# shcematics.net
KiCad netlist of a schematic drawn in Altium Designer
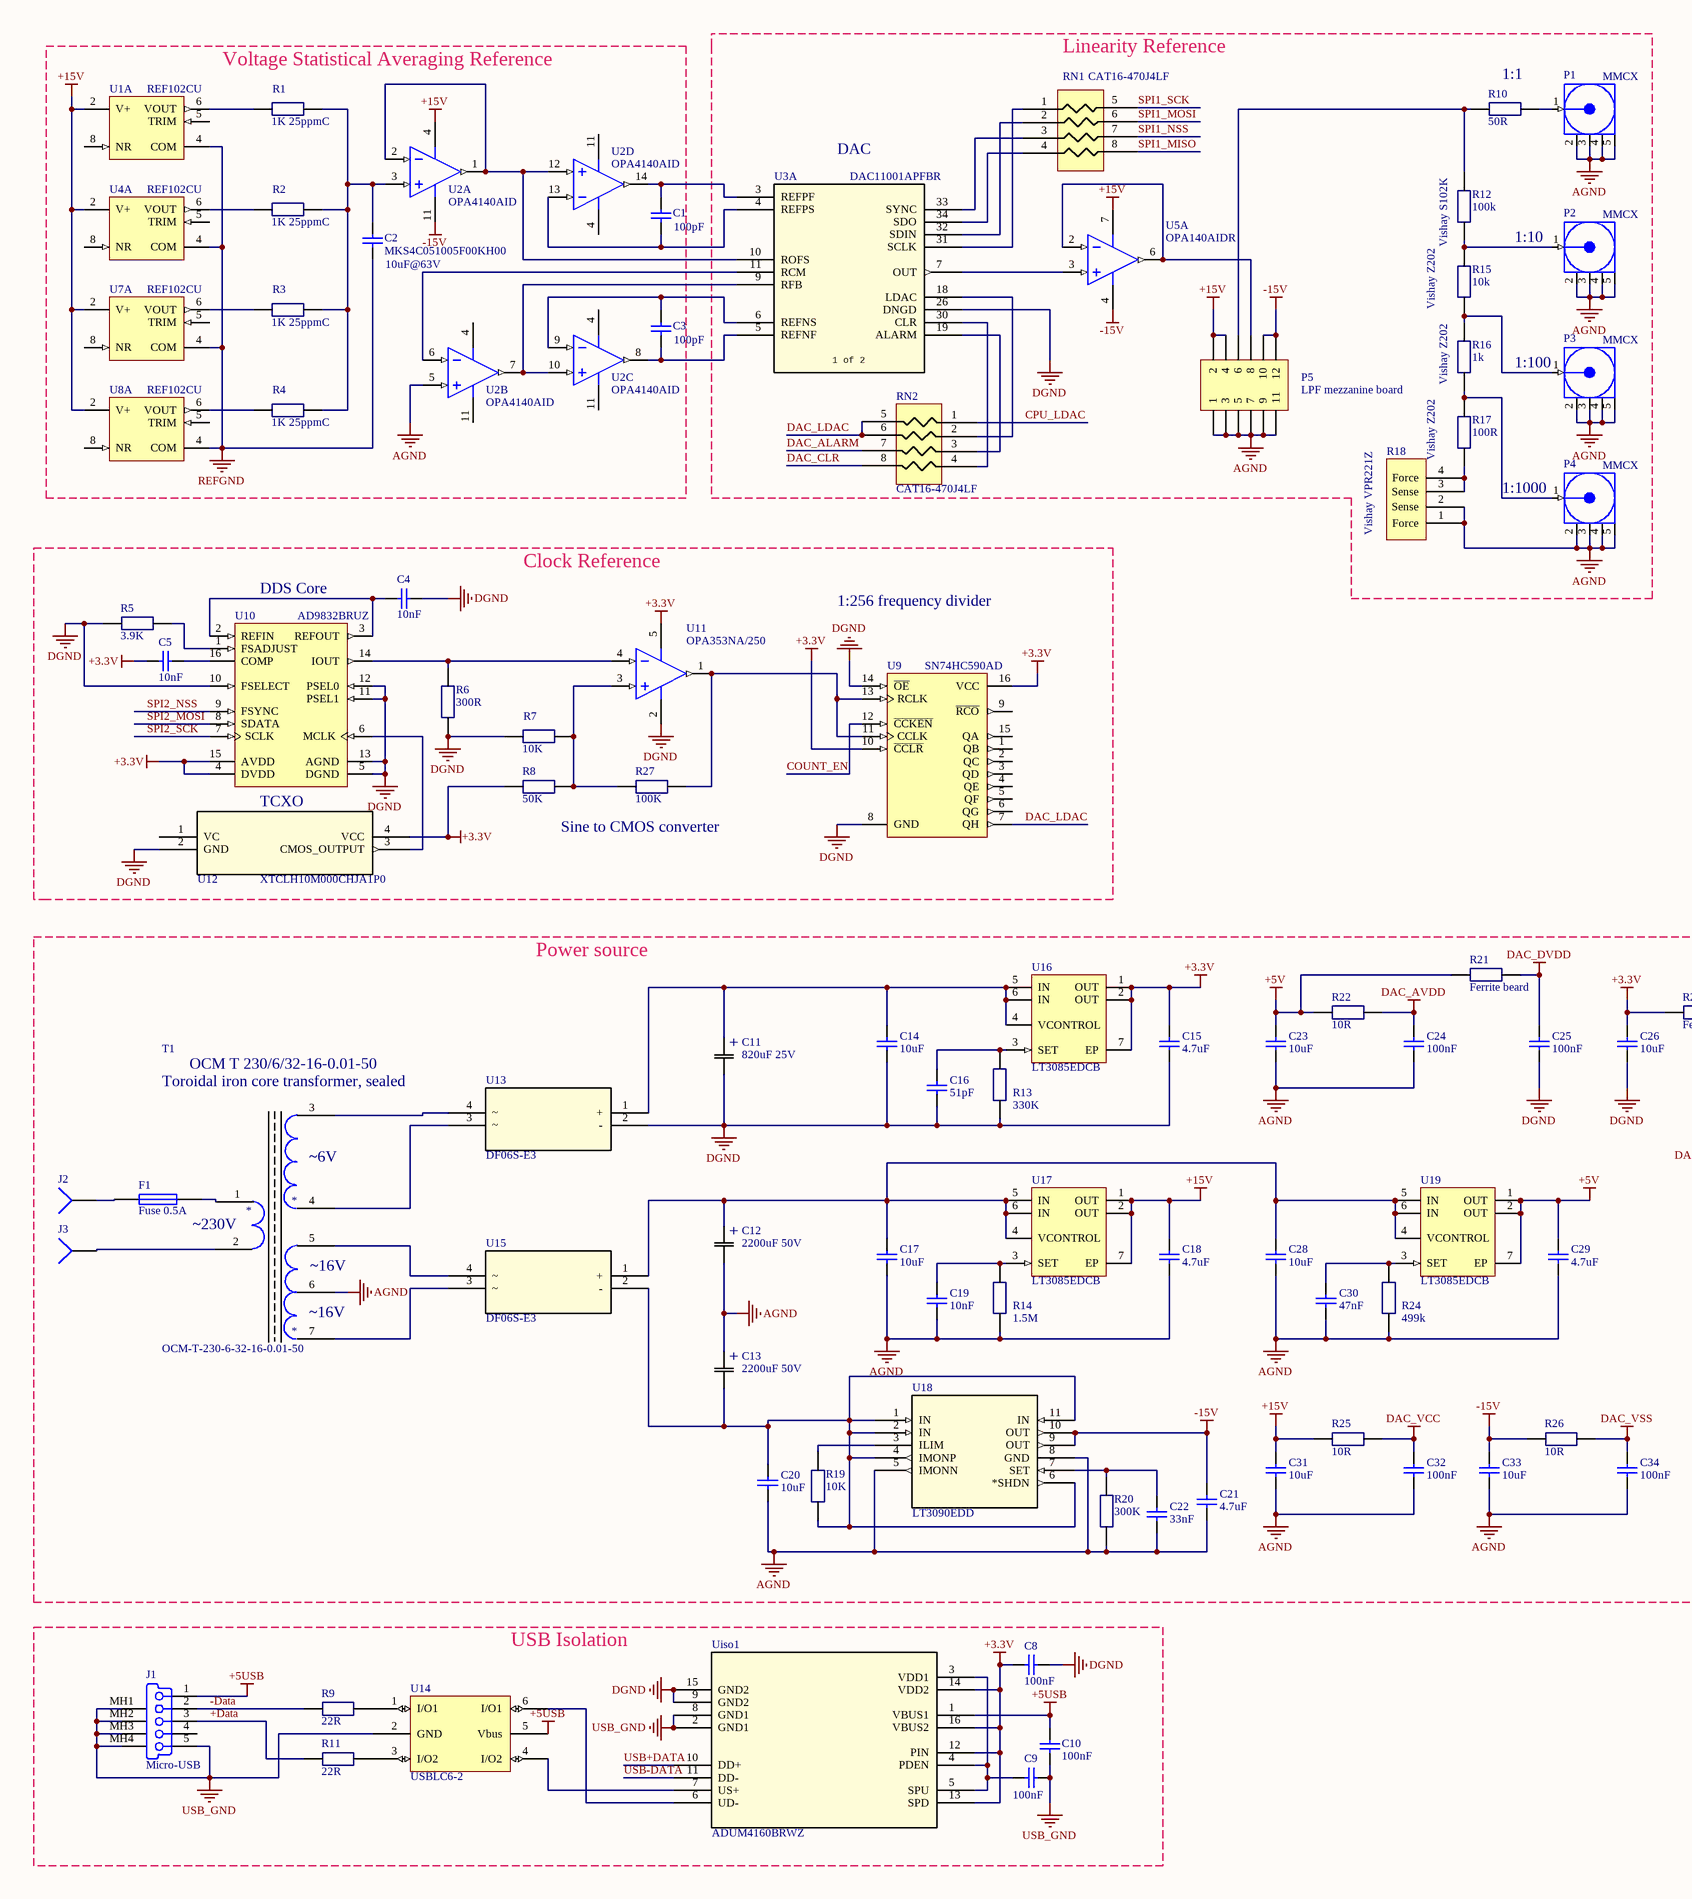
[diagram p0: shcematics.SchDoc, left]
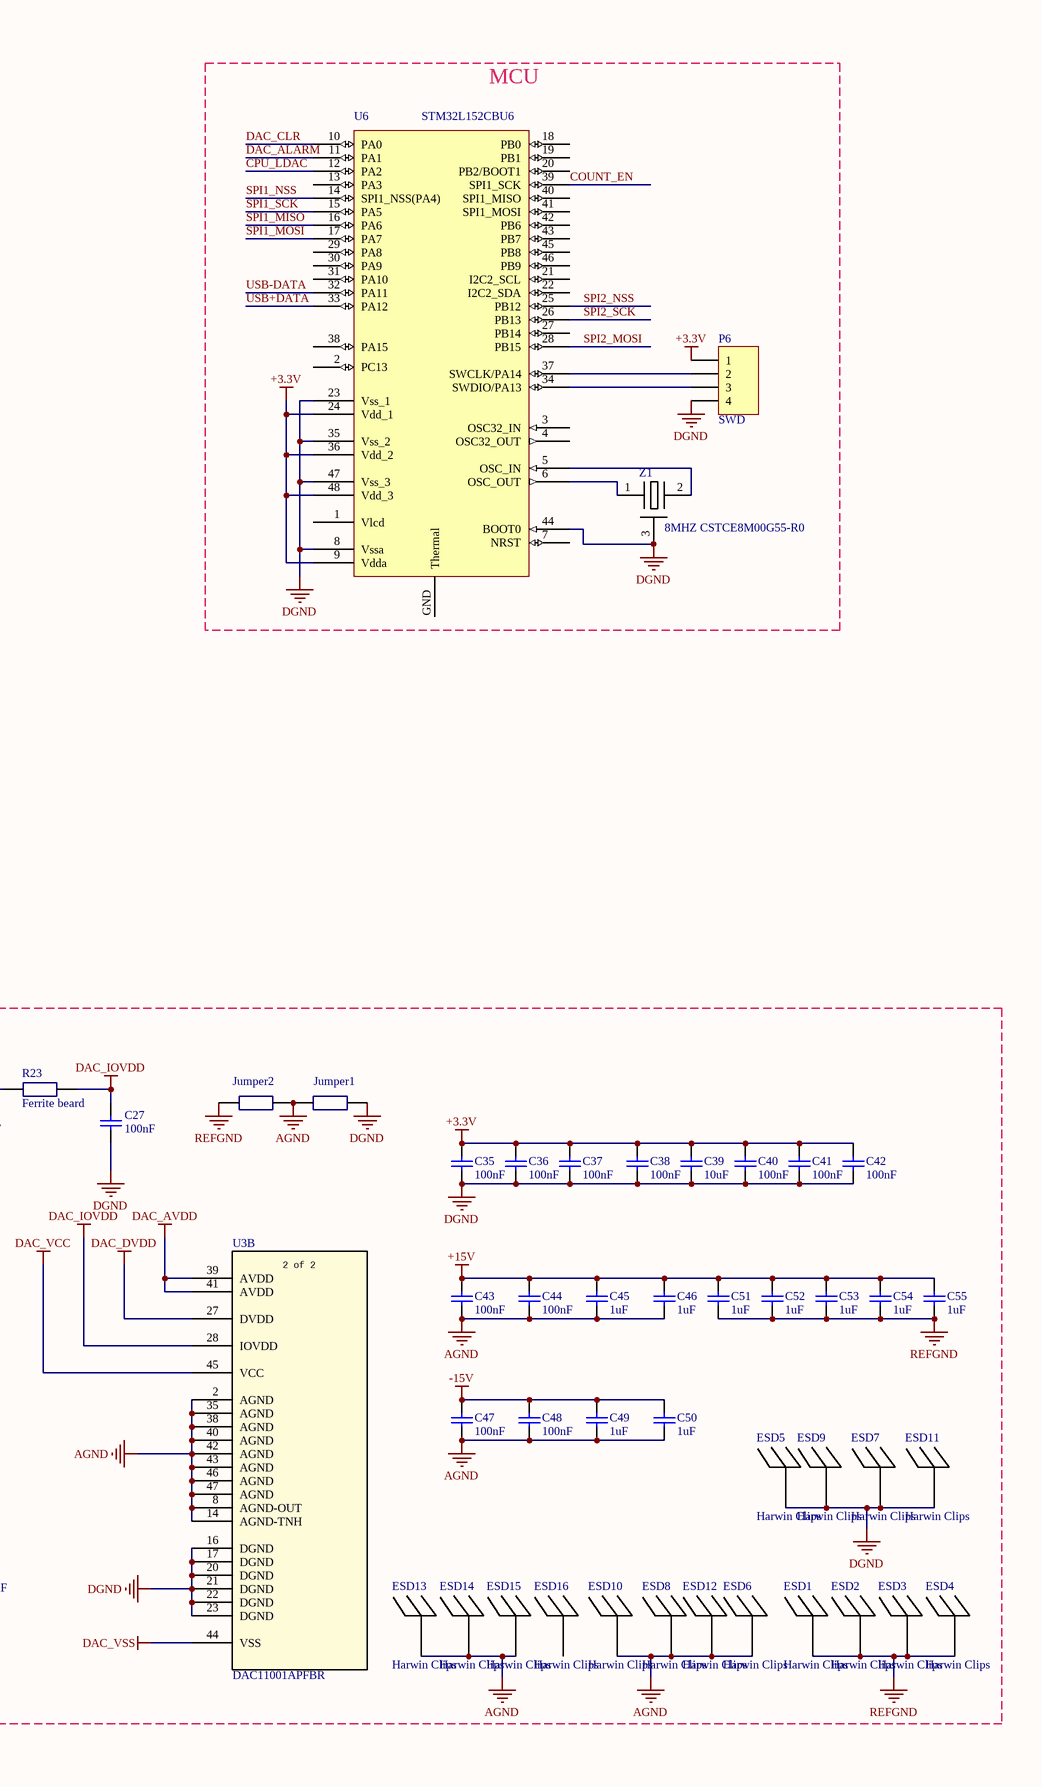
[diagram p1: shcematics.SchDoc, right]

(export (version "E")
  (design (tool "Eeschema 10.0.6"))
  (components
    (comp (ref "C1")
      (value "100pF")
      (footprint "0402")
      (description "Capacitor (Semiconductor SIM Model)")
      (fields (field (name "Comment") "Cap Semi") (field (name "PUBLISHER") "Altium Limited"))
      (libsource (lib "Miscellaneous Devices") (part "Cap Semi"))
    )
    (comp (ref "C2")
      (value "MKS4C051005F00KH00")
      (footprint "MKS4C051005F")
      (description "Capacitor")
      (fields (field (name "ALTIUM_VALUE") "10uF@63V") (field (name "PUBLISHER") "Altium Limited"))
      (libsource (lib "Miscellaneous Devices") (part "Cap"))
    )
    (comp (ref "C3")
      (value "100pF")
      (footprint "0402")
      (description "Capacitor (Semiconductor SIM Model)")
      (fields (field (name "Comment") "Cap Semi") (field (name "PUBLISHER") "Altium Limited"))
      (libsource (lib "Miscellaneous Devices") (part "Cap Semi"))
    )
    (comp (ref "C4")
      (value "10nF")
      (footprint "CAP 0603")
      (description "Capacitor (Semiconductor SIM Model)")
      (fields (field (name "PUBLISHER") "Altium Limited"))
      (libsource (lib "Miscellaneous Devices") (part "Cap Semi"))
    )
    (comp (ref "C5")
      (value "10nF")
      (footprint "CAP 0603")
      (description "Capacitor (Semiconductor SIM Model)")
      (fields (field (name "PUBLISHER") "Altium Limited"))
      (libsource (lib "Miscellaneous Devices") (part "Cap Semi"))
    )
    (comp (ref "C8")
      (value "100nF")
      (footprint "CAP 0603")
      (description "Capacitor (Semiconductor SIM Model)")
      (fields (field (name "PUBLISHER") "Altium Limited"))
      (libsource (lib "Miscellaneous Devices") (part "Cap Semi"))
    )
    (comp (ref "C9")
      (value "100nF")
      (footprint "CAP 0603")
      (description "Capacitor (Semiconductor SIM Model)")
      (fields (field (name "PUBLISHER") "Altium Limited"))
      (libsource (lib "Miscellaneous Devices") (part "Cap Semi"))
    )
    (comp (ref "C10")
      (value "100nF")
      (footprint "CAP 0603")
      (description "Capacitor (Semiconductor SIM Model)")
      (fields (field (name "PUBLISHER") "Altium Limited"))
      (libsource (lib "Miscellaneous Devices") (part "Cap Semi"))
    )
    (comp (ref "C11")
      (value "820uF 25V")
      (footprint "CAP_37M000_TDK")
      (description "No Description Available")
      (fields
        (field (name "MANUFACTURER_PART_NUMBER") "B41858D9337M000")
        (field (name "COPYRIGHT") "Copyright (C) 2018 Accelerated Designs. All rights reserved")
      )
      (libsource (lib "2021-01-20_20-15-04") (part "B41858D9337M000"))
    )
    (comp (ref "C12")
      (value "2200uF 50V")
      (footprint "CAP_37M000_TDK")
      (description "No Description Available")
      (fields
        (field (name "MANUFACTURER_PART_NUMBER") "B41858D9337M000")
        (field (name "COPYRIGHT") "Copyright (C) 2018 Accelerated Designs. All rights reserved")
      )
      (libsource (lib "2021-01-20_20-15-04") (part "B41858D9337M000"))
    )
    (comp (ref "C13")
      (value "2200uF 50V")
      (footprint "CAP_37M000_TDK")
      (description "No Description Available")
      (fields
        (field (name "MANUFACTURER_PART_NUMBER") "B41858D9337M000")
        (field (name "COPYRIGHT") "Copyright (C) 2018 Accelerated Designs. All rights reserved")
      )
      (libsource (lib "2021-01-20_20-15-04") (part "B41858D9337M000"))
    )
    (comp (ref "C14")
      (value "10uF")
      (footprint "C1206")
      (description "Capacitor (Semiconductor SIM Model)")
      (fields (field (name "PUBLISHER") "Altium Limited"))
      (libsource (lib "Miscellaneous Devices") (part "Cap Semi"))
    )
    (comp (ref "C15")
      (value "4.7uF")
      (footprint "C1206")
      (description "Capacitor (Semiconductor SIM Model)")
      (fields (field (name "PUBLISHER") "Altium Limited"))
      (libsource (lib "Miscellaneous Devices") (part "Cap Semi"))
    )
    (comp (ref "C16")
      (value "51pF")
      (footprint "CAP 0603")
      (description "Capacitor (Semiconductor SIM Model)")
      (fields (field (name "PUBLISHER") "Altium Limited"))
      (libsource (lib "Miscellaneous Devices") (part "Cap Semi"))
    )
    (comp (ref "C17")
      (value "10uF")
      (footprint "C1206")
      (description "Capacitor (Semiconductor SIM Model)")
      (fields (field (name "PUBLISHER") "Altium Limited"))
      (libsource (lib "Miscellaneous Devices") (part "Cap Semi"))
    )
    (comp (ref "C18")
      (value "4.7uF")
      (footprint "C1206")
      (description "Capacitor (Semiconductor SIM Model)")
      (fields (field (name "PUBLISHER") "Altium Limited"))
      (libsource (lib "Miscellaneous Devices") (part "Cap Semi"))
    )
    (comp (ref "C19")
      (value "10nF")
      (footprint "CAP 0603")
      (description "Capacitor (Semiconductor SIM Model)")
      (fields (field (name "PUBLISHER") "Altium Limited"))
      (libsource (lib "Miscellaneous Devices") (part "Cap Semi"))
    )
    (comp (ref "C20")
      (value "10uF")
      (footprint "C1206")
      (description "Capacitor (Semiconductor SIM Model)")
      (fields (field (name "PUBLISHER") "Altium Limited"))
      (libsource (lib "Miscellaneous Devices") (part "Cap Semi"))
    )
    (comp (ref "C21")
      (value "4.7uF")
      (footprint "C1206")
      (description "Capacitor (Semiconductor SIM Model)")
      (fields (field (name "PUBLISHER") "Altium Limited"))
      (libsource (lib "Miscellaneous Devices") (part "Cap Semi"))
    )
    (comp (ref "C22")
      (value "33nF")
      (footprint "CAP 0603")
      (description "Capacitor (Semiconductor SIM Model)")
      (fields (field (name "PUBLISHER") "Altium Limited"))
      (libsource (lib "Miscellaneous Devices") (part "Cap Semi"))
    )
    (comp (ref "C23")
      (value "10uF")
      (footprint "CAP 0603")
      (description "Capacitor (Semiconductor SIM Model)")
      (fields (field (name "PUBLISHER") "Altium Limited"))
      (libsource (lib "Miscellaneous Devices") (part "Cap Semi"))
    )
    (comp (ref "C24")
      (value "100nF")
      (footprint "CAP 0603")
      (description "Capacitor (Semiconductor SIM Model)")
      (fields (field (name "PUBLISHER") "Altium Limited"))
      (libsource (lib "Miscellaneous Devices") (part "Cap Semi"))
    )
    (comp (ref "C25")
      (value "100nF")
      (footprint "CAP 0603")
      (description "Capacitor (Semiconductor SIM Model)")
      (fields (field (name "PUBLISHER") "Altium Limited"))
      (libsource (lib "Miscellaneous Devices") (part "Cap Semi"))
    )
    (comp (ref "C26")
      (value "10uF")
      (footprint "CAP 0603")
      (description "Capacitor (Semiconductor SIM Model)")
      (fields (field (name "PUBLISHER") "Altium Limited"))
      (libsource (lib "Miscellaneous Devices") (part "Cap Semi"))
    )
    (comp (ref "C27")
      (value "100nF")
      (footprint "CAP 0603")
      (description "Capacitor (Semiconductor SIM Model)")
      (fields (field (name "PUBLISHER") "Altium Limited"))
      (libsource (lib "Miscellaneous Devices") (part "Cap Semi"))
    )
    (comp (ref "C28")
      (value "10uF")
      (footprint "C1206")
      (description "Capacitor (Semiconductor SIM Model)")
      (fields (field (name "PUBLISHER") "Altium Limited"))
      (libsource (lib "Miscellaneous Devices") (part "Cap Semi"))
    )
    (comp (ref "C29")
      (value "4.7uF")
      (footprint "C1206")
      (description "Capacitor (Semiconductor SIM Model)")
      (fields (field (name "PUBLISHER") "Altium Limited"))
      (libsource (lib "Miscellaneous Devices") (part "Cap Semi"))
    )
    (comp (ref "C30")
      (value "47nF")
      (footprint "CAP 0603")
      (description "Capacitor (Semiconductor SIM Model)")
      (fields (field (name "PUBLISHER") "Altium Limited"))
      (libsource (lib "Miscellaneous Devices") (part "Cap Semi"))
    )
    (comp (ref "C31")
      (value "10uF")
      (footprint "C1206")
      (description "Capacitor (Semiconductor SIM Model)")
      (fields (field (name "PUBLISHER") "Altium Limited"))
      (libsource (lib "Miscellaneous Devices") (part "Cap Semi"))
    )
    (comp (ref "C32")
      (value "100nF")
      (footprint "CAP 0603")
      (description "Capacitor (Semiconductor SIM Model)")
      (fields (field (name "PUBLISHER") "Altium Limited"))
      (libsource (lib "Miscellaneous Devices") (part "Cap Semi"))
    )
    (comp (ref "C33")
      (value "10uF")
      (footprint "C1206")
      (description "Capacitor (Semiconductor SIM Model)")
      (fields (field (name "PUBLISHER") "Altium Limited"))
      (libsource (lib "Miscellaneous Devices") (part "Cap Semi"))
    )
    (comp (ref "C34")
      (value "100nF")
      (footprint "CAP 0603")
      (description "Capacitor (Semiconductor SIM Model)")
      (fields (field (name "PUBLISHER") "Altium Limited"))
      (libsource (lib "Miscellaneous Devices") (part "Cap Semi"))
    )
    (comp (ref "C35")
      (value "100nF")
      (footprint "CAP 0603")
      (description "Capacitor (Semiconductor SIM Model)")
      (fields (field (name "PUBLISHER") "Altium Limited"))
      (libsource (lib "Miscellaneous Devices") (part "Cap Semi"))
    )
    (comp (ref "C36")
      (value "100nF")
      (footprint "CAP 0603")
      (description "Capacitor (Semiconductor SIM Model)")
      (fields (field (name "PUBLISHER") "Altium Limited"))
      (libsource (lib "Miscellaneous Devices") (part "Cap Semi"))
    )
    (comp (ref "C37")
      (value "100nF")
      (footprint "CAP 0603")
      (description "Capacitor (Semiconductor SIM Model)")
      (fields (field (name "PUBLISHER") "Altium Limited"))
      (libsource (lib "Miscellaneous Devices") (part "Cap Semi"))
    )
    (comp (ref "C38")
      (value "100nF")
      (footprint "CAP 0603")
      (description "Capacitor (Semiconductor SIM Model)")
      (fields (field (name "PUBLISHER") "Altium Limited"))
      (libsource (lib "Miscellaneous Devices") (part "Cap Semi"))
    )
    (comp (ref "C39")
      (value "10uF")
      (footprint "CAP 0603")
      (description "Capacitor (Semiconductor SIM Model)")
      (fields (field (name "PUBLISHER") "Altium Limited"))
      (libsource (lib "Miscellaneous Devices") (part "Cap Semi"))
    )
    (comp (ref "C40")
      (value "100nF")
      (footprint "CAP 0603")
      (description "Capacitor (Semiconductor SIM Model)")
      (fields (field (name "PUBLISHER") "Altium Limited"))
      (libsource (lib "Miscellaneous Devices") (part "Cap Semi"))
    )
    (comp (ref "C41")
      (value "100nF")
      (footprint "CAP 0603")
      (description "Capacitor (Semiconductor SIM Model)")
      (fields (field (name "PUBLISHER") "Altium Limited"))
      (libsource (lib "Miscellaneous Devices") (part "Cap Semi"))
    )
    (comp (ref "C42")
      (value "100nF")
      (footprint "CAP 0603")
      (description "Capacitor (Semiconductor SIM Model)")
      (fields (field (name "PUBLISHER") "Altium Limited"))
      (libsource (lib "Miscellaneous Devices") (part "Cap Semi"))
    )
    (comp (ref "C43")
      (value "100nF")
      (footprint "CAP 0603")
      (description "Capacitor (Semiconductor SIM Model)")
      (fields (field (name "PUBLISHER") "Altium Limited"))
      (libsource (lib "Miscellaneous Devices") (part "Cap Semi"))
    )
    (comp (ref "C44")
      (value "100nF")
      (footprint "CAP 0603")
      (description "Capacitor (Semiconductor SIM Model)")
      (fields (field (name "PUBLISHER") "Altium Limited"))
      (libsource (lib "Miscellaneous Devices") (part "Cap Semi"))
    )
    (comp (ref "C45")
      (value "1uF")
      (footprint "CAP 0603")
      (description "Capacitor (Semiconductor SIM Model)")
      (fields (field (name "PUBLISHER") "Altium Limited"))
      (libsource (lib "Miscellaneous Devices") (part "Cap Semi"))
    )
    (comp (ref "C46")
      (value "1uF")
      (footprint "CAP 0603")
      (description "Capacitor (Semiconductor SIM Model)")
      (fields (field (name "PUBLISHER") "Altium Limited"))
      (libsource (lib "Miscellaneous Devices") (part "Cap Semi"))
    )
    (comp (ref "C47")
      (value "100nF")
      (footprint "CAP 0603")
      (description "Capacitor (Semiconductor SIM Model)")
      (fields (field (name "PUBLISHER") "Altium Limited"))
      (libsource (lib "Miscellaneous Devices") (part "Cap Semi"))
    )
    (comp (ref "C48")
      (value "100nF")
      (footprint "CAP 0603")
      (description "Capacitor (Semiconductor SIM Model)")
      (fields (field (name "PUBLISHER") "Altium Limited"))
      (libsource (lib "Miscellaneous Devices") (part "Cap Semi"))
    )
    (comp (ref "C49")
      (value "1uF")
      (footprint "CAP 0603")
      (description "Capacitor (Semiconductor SIM Model)")
      (fields (field (name "PUBLISHER") "Altium Limited"))
      (libsource (lib "Miscellaneous Devices") (part "Cap Semi"))
    )
    (comp (ref "C50")
      (value "1uF")
      (footprint "CAP 0603")
      (description "Capacitor (Semiconductor SIM Model)")
      (fields (field (name "PUBLISHER") "Altium Limited"))
      (libsource (lib "Miscellaneous Devices") (part "Cap Semi"))
    )
    (comp (ref "C51")
      (value "1uF")
      (footprint "CAP 0603")
      (description "Capacitor (Semiconductor SIM Model)")
      (fields (field (name "PUBLISHER") "Altium Limited"))
      (libsource (lib "Miscellaneous Devices") (part "Cap Semi"))
    )
    (comp (ref "C52")
      (value "1uF")
      (footprint "CAP 0603")
      (description "Capacitor (Semiconductor SIM Model)")
      (fields (field (name "PUBLISHER") "Altium Limited"))
      (libsource (lib "Miscellaneous Devices") (part "Cap Semi"))
    )
    (comp (ref "C53")
      (value "1uF")
      (footprint "CAP 0603")
      (description "Capacitor (Semiconductor SIM Model)")
      (fields (field (name "PUBLISHER") "Altium Limited"))
      (libsource (lib "Miscellaneous Devices") (part "Cap Semi"))
    )
    (comp (ref "C54")
      (value "1uF")
      (footprint "CAP 0603")
      (description "Capacitor (Semiconductor SIM Model)")
      (fields (field (name "PUBLISHER") "Altium Limited"))
      (libsource (lib "Miscellaneous Devices") (part "Cap Semi"))
    )
    (comp (ref "C55")
      (value "1uF")
      (footprint "CAP 0603")
      (description "Capacitor (Semiconductor SIM Model)")
      (fields (field (name "PUBLISHER") "Altium Limited"))
      (libsource (lib "Miscellaneous Devices") (part "Cap Semi"))
    )
    (comp (ref "ESD1")
      (value "Harwin Clips")
      (footprint "HARWIN - S0981-46R - CLIP")
      (libsource (lib "My SCH library") (part "Harwin Clips"))
    )
    (comp (ref "ESD2")
      (value "Harwin Clips")
      (footprint "HARWIN - S0981-46R - CLIP")
      (libsource (lib "My SCH library") (part "Harwin Clips"))
    )
    (comp (ref "ESD3")
      (value "Harwin Clips")
      (footprint "HARWIN - S0981-46R - CLIP")
      (libsource (lib "My SCH library") (part "Harwin Clips"))
    )
    (comp (ref "ESD4")
      (value "Harwin Clips")
      (footprint "HARWIN - S0981-46R - CLIP")
      (libsource (lib "My SCH library") (part "Harwin Clips"))
    )
    (comp (ref "ESD5")
      (value "Harwin Clips")
      (footprint "HARWIN - S0981-46R - CLIP")
      (libsource (lib "My SCH library") (part "Harwin Clips"))
    )
    (comp (ref "ESD6")
      (value "Harwin Clips")
      (footprint "HARWIN - S0981-46R - CLIP")
      (libsource (lib "My SCH library") (part "Harwin Clips"))
    )
    (comp (ref "ESD7")
      (value "Harwin Clips")
      (footprint "HARWIN - S0981-46R - CLIP")
      (libsource (lib "My SCH library") (part "Harwin Clips"))
    )
    (comp (ref "ESD8")
      (value "Harwin Clips")
      (footprint "HARWIN - S0981-46R - CLIP")
      (libsource (lib "My SCH library") (part "Harwin Clips"))
    )
    (comp (ref "ESD9")
      (value "Harwin Clips")
      (footprint "HARWIN - S0981-46R - CLIP")
      (libsource (lib "My SCH library") (part "Harwin Clips"))
    )
    (comp (ref "ESD10")
      (value "Harwin Clips")
      (footprint "HARWIN - S0981-46R - CLIP")
      (libsource (lib "My SCH library") (part "Harwin Clips"))
    )
    (comp (ref "ESD11")
      (value "Harwin Clips")
      (footprint "HARWIN - S0981-46R - CLIP")
      (libsource (lib "My SCH library") (part "Harwin Clips"))
    )
    (comp (ref "ESD12")
      (value "Harwin Clips")
      (footprint "HARWIN - S0981-46R - CLIP")
      (libsource (lib "My SCH library") (part "Harwin Clips"))
    )
    (comp (ref "ESD13")
      (value "Harwin Clips")
      (footprint "HARWIN - S0981-46R - CLIP")
      (libsource (lib "My SCH library") (part "Harwin Clips"))
    )
    (comp (ref "ESD14")
      (value "Harwin Clips")
      (footprint "HARWIN - S0981-46R - CLIP")
      (libsource (lib "My SCH library") (part "Harwin Clips"))
    )
    (comp (ref "ESD15")
      (value "Harwin Clips")
      (footprint "HARWIN - S0981-46R - CLIP")
      (libsource (lib "My SCH library") (part "Harwin Clips"))
    )
    (comp (ref "ESD16")
      (value "Harwin Clips")
      (footprint "HARWIN - S0981-46R - CLIP")
      (libsource (lib "My SCH library") (part "Harwin Clips"))
    )
    (comp (ref "F1")
      (value "Fuse 0.5A")
      (footprint "FUSE")
      (description "Fuse")
      (fields (field (name "PUBLISHER") "Altium Limited"))
      (libsource (lib "Miscellaneous Devices") (part "Fuse 1"))
    )
    (comp (ref "J1")
      (value "Micro-USB")
      (footprint "10118193-0001LF")
      (libsource (lib "Molex Serial Bus Mini USB") (part "0481900001"))
    )
    (comp (ref "J2")
      (value "Socket")
      (footprint "PIN1")
      (fields (field (name "PUBLISHER") "Altium Limited"))
      (libsource (lib "Miscellaneous Connectors") (part "Socket"))
    )
    (comp (ref "J3")
      (value "Socket")
      (footprint "PIN1")
      (fields (field (name "PUBLISHER") "Altium Limited"))
      (libsource (lib "Miscellaneous Connectors") (part "Socket"))
    )
    (comp (ref "Jumper1")
      (value "~")
      (footprint "0402 jumper")
      (libsource (lib "Микрон-3") (part "Resistor 0805"))
    )
    (comp (ref "Jumper2")
      (value "~")
      (footprint "0402 jumper")
      (libsource (lib "Микрон-3") (part "Resistor 0805"))
    )
    (comp (ref "P1")
      (value "MMCX")
      (footprint "MMCX2.54-V5")
      (description "RF Coaxial PCB Connector, MMCX; Thru-Hole, Vertical Mount Plug,  50 Ohm Impedance")
      (fields (field (name "PUBLISHER") "Altium Limited"))
      (libsource (lib "Miscellaneous Connectors") (part "COAX-M"))
    )
    (comp (ref "P2")
      (value "MMCX")
      (footprint "MMCX2.54-V5")
      (description "RF Coaxial PCB Connector, MMCX; Thru-Hole, Vertical Mount Plug,  50 Ohm Impedance")
      (fields (field (name "PUBLISHER") "Altium Limited"))
      (libsource (lib "Miscellaneous Connectors") (part "COAX-M"))
    )
    (comp (ref "P3")
      (value "MMCX")
      (footprint "MMCX2.54-V5")
      (description "RF Coaxial PCB Connector, MMCX; Thru-Hole, Vertical Mount Plug,  50 Ohm Impedance")
      (fields (field (name "PUBLISHER") "Altium Limited"))
      (libsource (lib "Miscellaneous Connectors") (part "COAX-M"))
    )
    (comp (ref "P4")
      (value "MMCX")
      (footprint "MMCX2.54-V5")
      (description "RF Coaxial PCB Connector, MMCX; Thru-Hole, Vertical Mount Plug,  50 Ohm Impedance")
      (fields (field (name "PUBLISHER") "Altium Limited"))
      (libsource (lib "Miscellaneous Connectors") (part "COAX-M"))
    )
    (comp (ref "P5")
      (value "LPF mezzanine board")
      (footprint "HDR2X6")
      (description "Header, 6-Pin, Dual row")
      (fields (field (name "PUBLISHER") "Altium Limited"))
      (libsource (lib "Miscellaneous Connectors") (part "Header 6X2"))
    )
    (comp (ref "P6")
      (value "SWD")
      (footprint "HDR1X4")
      (description "Header, 4-Pin")
      (fields (field (name "PUBLISHER") "Altium Limited"))
      (libsource (lib "Miscellaneous Connectors") (part "Header 4"))
    )
    (comp (ref "R1")
      (value "1K 25ppmC")
      (footprint "1608[0603]")
      (libsource (lib "Микрон-3") (part "Resistor 0805"))
    )
    (comp (ref "R2")
      (value "1K 25ppmC")
      (footprint "1608[0603]")
      (libsource (lib "Микрон-3") (part "Resistor 0805"))
    )
    (comp (ref "R3")
      (value "1K 25ppmC")
      (footprint "1608[0603]")
      (libsource (lib "Микрон-3") (part "Resistor 0805"))
    )
    (comp (ref "R4")
      (value "1K 25ppmC")
      (footprint "1608[0603]")
      (libsource (lib "Микрон-3") (part "Resistor 0805"))
    )
    (comp (ref "R5")
      (value "3.9K")
      (footprint "1608[0603]")
      (libsource (lib "Микрон-3") (part "Resistor 0805"))
    )
    (comp (ref "R6")
      (value "300R")
      (footprint "Yegeo 0603")
      (libsource (lib "Микрон-3") (part "Resistor 0805"))
    )
    (comp (ref "R7")
      (value "10K")
      (footprint "Yegeo 0603")
      (libsource (lib "Микрон-3") (part "Resistor 0805"))
    )
    (comp (ref "R8")
      (value "50K")
      (footprint "Yegeo 0603")
      (libsource (lib "Микрон-3") (part "Resistor 0805"))
    )
    (comp (ref "R9")
      (value "22R")
      (footprint "1608[0603]")
      (libsource (lib "Микрон-3") (part "Resistor 0805"))
    )
    (comp (ref "R10")
      (value "50R")
      (footprint "1608[0603]")
      (libsource (lib "Микрон-3") (part "Resistor 0805"))
    )
    (comp (ref "R11")
      (value "22R")
      (footprint "1608[0603]")
      (libsource (lib "Микрон-3") (part "Resistor 0805"))
    )
    (comp (ref "R12")
      (value "100k")
      (footprint "Vishay S102K")
      (fields (field (name "ORDER") "Vishay S102K"))
      (libsource (lib "Микрон-3") (part "Resistor 0805"))
    )
    (comp (ref "R13")
      (value "330K")
      (footprint "1608[0603]")
      (libsource (lib "Микрон-3") (part "Resistor 0805"))
    )
    (comp (ref "R14")
      (value "1.5M")
      (footprint "6-0805_M")
      (libsource (lib "Микрон-3") (part "Resistor 0805"))
    )
    (comp (ref "R15")
      (value "10k")
      (footprint "Vishay Z202")
      (fields (field (name "ORDER") "Vishay Z202"))
      (libsource (lib "Микрон-3") (part "Resistor 0805"))
    )
    (comp (ref "R16")
      (value "1k")
      (footprint "Vishay Z202")
      (fields (field (name "ORDER") "Vishay Z202"))
      (libsource (lib "Микрон-3") (part "Resistor 0805"))
    )
    (comp (ref "R17")
      (value "100R")
      (footprint "Vishay Z202")
      (fields (field (name "ORDER") "Vishay Z202"))
      (libsource (lib "Микрон-3") (part "Resistor 0805"))
    )
    (comp (ref "R18")
      (value "Vishay VPR221Z")
      (footprint "VISHAY VPR221Z")
      (libsource (lib "My SCH library") (part "VISHAY VPR221Z"))
    )
    (comp (ref "R19")
      (value "10K")
      (footprint "1608[0603]")
      (libsource (lib "Микрон-3") (part "Resistor 0805"))
    )
    (comp (ref "R20")
      (value "300K")
      (footprint "1608[0603]")
      (libsource (lib "Микрон-3") (part "Resistor 0805"))
    )
    (comp (ref "R21")
      (value "Ferrite beard")
      (footprint "CC1206JRNPOBBN100")
      (libsource (lib "Микрон-3") (part "Resistor 0805"))
    )
    (comp (ref "R22")
      (value "10R")
      (footprint "1608[0603]")
      (libsource (lib "Микрон-3") (part "Resistor 0805"))
    )
    (comp (ref "R23")
      (value "Ferrite beard")
      (footprint "CC1206JRNPOBBN100")
      (libsource (lib "Микрон-3") (part "Resistor 0805"))
    )
    (comp (ref "R24")
      (value "499k")
      (footprint "1608[0603]")
      (libsource (lib "Микрон-3") (part "Resistor 0805"))
    )
    (comp (ref "R25")
      (value "10R")
      (footprint "1608[0603]")
      (libsource (lib "Микрон-3") (part "Resistor 0805"))
    )
    (comp (ref "R26")
      (value "10R")
      (footprint "1608[0603]")
      (libsource (lib "Микрон-3") (part "Resistor 0805"))
    )
    (comp (ref "R27")
      (value "100K")
      (footprint "Yegeo 0603")
      (libsource (lib "Микрон-3") (part "Resistor 0805"))
    )
    (comp (ref "RN1")
      (value "CAT16-470J4LF")
      (footprint "CAT16-470J4LF")
      (libsource (lib "") (part "CAT16-470J4LF_1"))
    )
    (comp (ref "RN2")
      (value "CAT16-470J4LF")
      (footprint "CAT16-470J4LF")
      (libsource (lib "My SCH library") (part "CAT16-470J4LF"))
    )
    (comp (ref "T1")
      (value "OCM-T-230-6-32-16-0.01-50")
      (footprint "OCM-T-230-6-32-16-0.01-50")
      (libsource (lib "My SCH library") (part "OCM-T-230-6-32-16-0.01-50"))
    )
    (comp (ref "U1")
      (value "REF102CU")
      (footprint "TI-D8_N")
      (description "10 V Precision Voltage Reference, -25 to 85 degC, 8-pin SOIC (D), Green (RoHS & no Sb/Br)")
      (fields (field (name "MANUFACTURER") "Texas Instruments"))
      (libsource (lib "TI Power Management Series Voltage Reference") (part "REF102CU"))
    )
    (comp (ref "U2")
      (value "OPA4140AID")
      (footprint "TI-D14_N")
      (fields (field (name "MANUFACTURER") "Texas Instruments"))
      (libsource (lib "TI Amplifiers and Linear Operational Amplifier Precision Amplifier Part One") (part "OPA4140AID"))
    )
    (comp (ref "U3")
      (value "DAC11001APFBR")
      (footprint "QFP_APFBR_TEX")
      (description "No Description Available")
      (fields (field (name "COPYRIGHT") "Copyright (C) 2018 Accelerated Designs. All rights reserved"))
      (libsource (lib "2021-01-15_13-58-29") (part "DAC11001APFBR"))
    )
    (comp (ref "U4")
      (value "REF102CU")
      (footprint "TI-D8_N")
      (description "10 V Precision Voltage Reference, -25 to 85 degC, 8-pin SOIC (D), Green (RoHS & no Sb/Br)")
      (fields (field (name "MANUFACTURER") "Texas Instruments"))
      (libsource (lib "TI Power Management Series Voltage Reference") (part "REF102CU"))
    )
    (comp (ref "U5")
      (value "OPA140AIDR")
      (footprint "TI-D8_N")
      (fields (field (name "MANUFACTURER") "Texas Instruments"))
      (libsource (lib "TI Amplifiers and Linear Operational Amplifier Precision Amplifier Part One") (part "OPA140AIDR"))
    )
    (comp (ref "U6")
      (value "STM32L152CBU6")
      (footprint "UFQFPN48")
      (libsource (lib "My SCH library") (part "STM32L152CBU6"))
    )
    (comp (ref "U7")
      (value "REF102CU")
      (footprint "TI-D8_N")
      (description "10 V Precision Voltage Reference, -25 to 85 degC, 8-pin SOIC (D), Green (RoHS & no Sb/Br)")
      (fields (field (name "MANUFACTURER") "Texas Instruments"))
      (libsource (lib "TI Power Management Series Voltage Reference") (part "REF102CU"))
    )
    (comp (ref "U8")
      (value "REF102CU")
      (footprint "TI-D8_N")
      (description "10 V Precision Voltage Reference, -25 to 85 degC, 8-pin SOIC (D), Green (RoHS & no Sb/Br)")
      (fields (field (name "MANUFACTURER") "Texas Instruments"))
      (libsource (lib "TI Power Management Series Voltage Reference") (part "REF102CU"))
    )
    (comp (ref "U9")
      (value "SN74HC590AD")
      (footprint "D016_N")
      (description "8-Bit Binary Counter with 3-State Output Registers")
      (fields (field (name "PUBLISHER") "Altium Limited"))
      (libsource (lib "TI Logic Counter") (part "SN74HC590AD"))
    )
    (comp (ref "U10")
      (value "AD9832BRUZ")
      (footprint "ADI-RU-16_N")
      (description "25 MHz Direct Digital Synthesizer, Waveform Generator, 10-Bit, Serial, RU-16, 96 Tube, Pb-Free")
      (libsource (lib "Analog Devices RF IF Direct Digital Synthesis") (part "AD9832BRUZ"))
    )
    (comp (ref "U11")
      (value "OPA353NA/250")
      (footprint "TI-DBV5_N")
      (fields (field (name "MANUFACTURER") "Texas Instruments"))
      (libsource (lib "TI Amplifiers and Linear Operational Amplifier Precision Amplifier Part One") (part "OPA353NA/250"))
    )
    (comp (ref "U12")
      (value "XTCLH10M000CHJA1P0")
      (footprint "XTCLH20M000CHJA0P0_MUR")
      (description "No Description Available")
      (fields
        (field (name "MANUFACTURER_PART_NUMBER") "XTCLH20M000CHJA0P0")
        (field (name "COPYRIGHT") "Copyright (C) 2018 Accelerated Designs. All rights reserved")
      )
      (libsource (lib "2021-01-16_08-30-23") (part "XTCLH20M000CHJA0P0"))
    )
    (comp (ref "U13")
      (value "DF06S-E3")
      (footprint "SO4_DFS_VIS-M")
      (description "No Description Available")
      (fields (field (name "COPYRIGHT") "Copyright (C) 2018 Accelerated Designs. All rights reserved"))
      (libsource (lib "2021-01-20_20-05-57") (part "DF06S-E3"))
    )
    (comp (ref "U14")
      (value "USBLC6-2")
      (footprint "SOT23-6L")
      (libsource (lib "Микрон-3") (part "USBLC6-2"))
    )
    (comp (ref "U15")
      (value "DF06S-E3")
      (footprint "SO4_DFS_VIS-M")
      (description "No Description Available")
      (fields (field (name "COPYRIGHT") "Copyright (C) 2018 Accelerated Designs. All rights reserved"))
      (libsource (lib "2021-01-20_20-05-57") (part "DF06S-E3"))
    )
    (comp (ref "U16")
      (value "LT3085EDCB")
      (footprint "LT-DCB-6_V")
      (fields (field (name "MANUFACTURER") "Linear Technology") (field (name "PARTNUMBER") "LT3085EDCB#PBF"))
      (libsource (lib "Linear Technology Power Management Current Sources") (part "LT3085EDCB#PBF"))
    )
    (comp (ref "U17")
      (value "LT3085EDCB")
      (footprint "LT-DCB-6_V")
      (fields (field (name "MANUFACTURER") "Linear Technology") (field (name "PARTNUMBER") "LT3085EDCB#PBF"))
      (libsource (lib "Linear Technology Power Management Current Sources") (part "LT3085EDCB#PBF"))
    )
    (comp (ref "U18")
      (value "LT3090EDD")
      (footprint "DFN-10_DD")
      (description "Imported")
      (fields (field (name "MANUFACTURER_PART_NUMBER") "lt3090edd#pbf"))
      (libsource (lib "2017-08-07_08-21-16") (part "LT3090EDDPBF"))
    )
    (comp (ref "U19")
      (value "LT3085EDCB")
      (footprint "LT-DCB-6_V")
      (fields (field (name "MANUFACTURER") "Linear Technology") (field (name "PARTNUMBER") "LT3085EDCB#PBF"))
      (libsource (lib "Linear Technology Power Management Current Sources") (part "LT3085EDCB#PBF"))
    )
    (comp (ref "Uiso1")
      (value "ADUM4160BRWZ")
      (footprint "RW_16_ADI")
      (description "No Description Available")
      (fields (field (name "COPYRIGHT") "Copyright (C) 2018 Accelerated Designs. All rights reserved"))
      (libsource (lib "2021-01-20_09-44-58") (part "ADUM4160BRWZ"))
    )
    (comp (ref "Z1")
      (value "8MHZ CSTCE8M00G55-R0")
      (footprint "PRQV8.00CR5010Y000")
      (libsource (lib "My SCH library") (part "8MHZ_cap"))
    )
  )
  (nets
    (net (code "1") (name "+3.3V") (class "Default")
      (node (ref "C15") (pin "1") (pinfunction "1_1") (pintype "passive"))
      (node (ref "C26") (pin "1") (pinfunction "1_1") (pintype "passive"))
      (node (ref "C35") (pin "2") (pinfunction "2_2") (pintype "passive"))
      (node (ref "C36") (pin "2") (pinfunction "2_2") (pintype "passive"))
      (node (ref "C37") (pin "2") (pinfunction "2_2") (pintype "passive"))
      (node (ref "C38") (pin "2") (pinfunction "2_2") (pintype "passive"))
      (node (ref "C39") (pin "2") (pinfunction "2_2") (pintype "passive"))
      (node (ref "C40") (pin "2") (pinfunction "2_2") (pintype "passive"))
      (node (ref "C41") (pin "2") (pinfunction "2_2") (pintype "passive"))
      (node (ref "C42") (pin "2") (pinfunction "2_2") (pintype "passive"))
      (node (ref "C5") (pin "1") (pinfunction "1_1") (pintype "passive"))
      (node (ref "C8") (pin "2") (pinfunction "2_2") (pintype "passive"))
      (node (ref "P6") (pin "1") (pinfunction "1_1") (pintype "passive"))
      (node (ref "R23") (pin "2") (pinfunction "2_2") (pintype "passive"))
      (node (ref "R8") (pin "2") (pinfunction "2_2") (pintype "passive"))
      (node (ref "U10") (pin "15") (pinfunction "AVDD_15") (pintype "power_in"))
      (node (ref "U10") (pin "4") (pinfunction "DVDD_4") (pintype "power_in"))
      (node (ref "U11") (pin "5") (pinfunction "V+_5") (pintype "power_in"))
      (node (ref "U12") (pin "4") (pinfunction "VCC_4") (pintype "power_in"))
      (node (ref "U16") (pin "1") (pinfunction "OUT_1") (pintype "power_in"))
      (node (ref "U16") (pin "2") (pinfunction "OUT_2") (pintype "power_in"))
      (node (ref "U16") (pin "7") (pinfunction "EP_7") (pintype "power_in"))
      (node (ref "U6") (pin "24") (pinfunction "Vdd_1_24") (pintype "power_in"))
      (node (ref "U6") (pin "36") (pinfunction "Vdd_2_36") (pintype "power_in"))
      (node (ref "U6") (pin "48") (pinfunction "Vdd_3_48") (pintype "power_in"))
      (node (ref "U6") (pin "9") (pinfunction "Vdda_9") (pintype "power_in"))
      (node (ref "U9") (pin "10") (pinfunction "~{CCLR}_10") (pintype "input"))
      (node (ref "U9") (pin "16") (pinfunction "VCC_16") (pintype "power_in"))
      (node (ref "Uiso1") (pin "12") (pinfunction "PIN_12") (pintype "passive"))
      (node (ref "Uiso1") (pin "13") (pinfunction "SPD_13") (pintype "passive"))
      (node (ref "Uiso1") (pin "14") (pinfunction "VDD2_14") (pintype "passive"))
      (node (ref "Uiso1") (pin "16") (pinfunction "VBUS2_16") (pintype "passive"))
    )
    (net (code "2") (name "+5USB") (class "Default")
      (node (ref "C10") (pin "2") (pinfunction "2_2") (pintype "passive"))
      (node (ref "J1") (pin "1") (pinfunction "V_BUS_(5V)_1") (pintype "passive"))
      (node (ref "U14") (pin "5") (pinfunction "Vbus_5") (pintype "power_in"))
      (node (ref "Uiso1") (pin "1") (pinfunction "VBUS1_1") (pintype "passive"))
    )
    (net (code "3") (name "+5V") (class "Default")
      (node (ref "C23") (pin "1") (pinfunction "1_1") (pintype "passive"))
      (node (ref "C29") (pin "1") (pinfunction "1_1") (pintype "passive"))
      (node (ref "R21") (pin "2") (pinfunction "2_2") (pintype "passive"))
      (node (ref "R22") (pin "2") (pinfunction "2_2") (pintype "passive"))
      (node (ref "U19") (pin "1") (pinfunction "OUT_1") (pintype "power_in"))
      (node (ref "U19") (pin "2") (pinfunction "OUT_2") (pintype "power_in"))
      (node (ref "U19") (pin "7") (pinfunction "EP_7") (pintype "power_in"))
    )
    (net (code "4") (name "+15V") (class "Default")
      (node (ref "C18") (pin "1") (pinfunction "1_1") (pintype "passive"))
      (node (ref "C31") (pin "1") (pinfunction "1_1") (pintype "passive"))
      (node (ref "C43") (pin "2") (pinfunction "2_2") (pintype "passive"))
      (node (ref "C44") (pin "2") (pinfunction "2_2") (pintype "passive"))
      (node (ref "C45") (pin "2") (pinfunction "2_2") (pintype "passive"))
      (node (ref "C46") (pin "2") (pinfunction "2_2") (pintype "passive"))
      (node (ref "C51") (pin "2") (pinfunction "2_2") (pintype "passive"))
      (node (ref "C52") (pin "2") (pinfunction "2_2") (pintype "passive"))
      (node (ref "C53") (pin "2") (pinfunction "2_2") (pintype "passive"))
      (node (ref "C54") (pin "2") (pinfunction "2_2") (pintype "passive"))
      (node (ref "C55") (pin "2") (pinfunction "2_2") (pintype "passive"))
      (node (ref "P5") (pin "2") (pinfunction "2_2") (pintype "passive"))
      (node (ref "P5") (pin "4") (pinfunction "4_4") (pintype "passive"))
      (node (ref "R25") (pin "2") (pinfunction "2_2") (pintype "passive"))
      (node (ref "U1") (pin "2") (pinfunction "V+_2") (pintype "power_in"))
      (node (ref "U17") (pin "1") (pinfunction "OUT_1") (pintype "power_in"))
      (node (ref "U17") (pin "2") (pinfunction "OUT_2") (pintype "power_in"))
      (node (ref "U17") (pin "7") (pinfunction "EP_7") (pintype "power_in"))
      (node (ref "U2") (pin "4") (pinfunction "V+_4") (pintype "power_in"))
      (node (ref "U4") (pin "2") (pinfunction "V+_2") (pintype "power_in"))
      (node (ref "U5") (pin "7") (pinfunction "V+_7") (pintype "power_in"))
      (node (ref "U7") (pin "2") (pinfunction "V+_2") (pintype "power_in"))
      (node (ref "U8") (pin "2") (pinfunction "V+_2") (pintype "power_in"))
    )
    (net (code "5") (name "-15V") (class "Default")
      (node (ref "C21") (pin "1") (pinfunction "1_1") (pintype "passive"))
      (node (ref "C33") (pin "1") (pinfunction "1_1") (pintype "passive"))
      (node (ref "C47") (pin "2") (pinfunction "2_2") (pintype "passive"))
      (node (ref "C48") (pin "2") (pinfunction "2_2") (pintype "passive"))
      (node (ref "C49") (pin "2") (pinfunction "2_2") (pintype "passive"))
      (node (ref "C50") (pin "2") (pinfunction "2_2") (pintype "passive"))
      (node (ref "P5") (pin "10") (pinfunction "10_10") (pintype "passive"))
      (node (ref "P5") (pin "12") (pinfunction "12_12") (pintype "passive"))
      (node (ref "R26") (pin "2") (pinfunction "2_2") (pintype "passive"))
      (node (ref "U18") (pin "10") (pinfunction "OUT_10") (pintype "output"))
      (node (ref "U18") (pin "9") (pinfunction "OUT_9") (pintype "output"))
      (node (ref "U2") (pin "11") (pinfunction "V-_11") (pintype "power_in"))
      (node (ref "U5") (pin "4") (pinfunction "V-_4") (pintype "power_in"))
    )
    (net (code "6") (name "/+Data") (class "Default")
      (node (ref "J1") (pin "3") (pinfunction "D+_3") (pintype "passive"))
      (node (ref "R11") (pin "2") (pinfunction "2_2") (pintype "passive"))
    )
    (net (code "7") (name "/-Data") (class "Default")
      (node (ref "J1") (pin "2") (pinfunction "D-_2") (pintype "passive"))
      (node (ref "R9") (pin "2") (pinfunction "2_2") (pintype "passive"))
    )
    (net (code "8") (name "/COUNT_EN") (class "Default")
      (node (ref "U6") (pin "39") (pinfunction "SPI1_SCK_39") (pintype "bidirectional"))
      (node (ref "U9") (pin "12") (pinfunction "~{CCKEN}_12") (pintype "input"))
    )
    (net (code "9") (name "/CPU_LDAC") (class "Default")
      (node (ref "RN2") (pin "1") (pinfunction "1_1") (pintype "passive"))
      (node (ref "U6") (pin "12") (pinfunction "PA2_12") (pintype "bidirectional"))
    )
    (net (code "10") (name "/DAC_ALARM") (class "Default")
      (node (ref "RN2") (pin "7") (pinfunction "7_7") (pintype "passive"))
      (node (ref "U6") (pin "11") (pinfunction "PA1_11") (pintype "bidirectional"))
    )
    (net (code "11") (name "/DAC_CLR") (class "Default")
      (node (ref "RN2") (pin "8") (pinfunction "8_8") (pintype "passive"))
      (node (ref "U6") (pin "10") (pinfunction "PA0_10") (pintype "bidirectional"))
    )
    (net (code "12") (name "/DAC_LDAC") (class "Default")
      (node (ref "RN2") (pin "5") (pinfunction "5_5") (pintype "passive"))
      (node (ref "RN2") (pin "6") (pinfunction "6_6") (pintype "passive"))
      (node (ref "U9") (pin "7") (pinfunction "QH_7") (pintype "output"))
    )
    (net (code "13") (name "/SPI1_MISO") (class "Default")
      (node (ref "RN1") (pin "8") (pinfunction "8_8") (pintype "passive"))
      (node (ref "U6") (pin "16") (pinfunction "PA6_16") (pintype "bidirectional"))
    )
    (net (code "14") (name "/SPI1_MOSI") (class "Default")
      (node (ref "RN1") (pin "6") (pinfunction "6_6") (pintype "passive"))
      (node (ref "U6") (pin "17") (pinfunction "PA7_17") (pintype "bidirectional"))
    )
    (net (code "15") (name "/SPI1_NSS") (class "Default")
      (node (ref "RN1") (pin "7") (pinfunction "7_7") (pintype "passive"))
      (node (ref "U6") (pin "14") (pinfunction "SPI1_NSS(PA4)_14") (pintype "bidirectional"))
    )
    (net (code "16") (name "/SPI1_SCK") (class "Default")
      (node (ref "RN1") (pin "5") (pinfunction "5_5") (pintype "passive"))
      (node (ref "U6") (pin "15") (pinfunction "PA5_15") (pintype "bidirectional"))
    )
    (net (code "17") (name "/SPI2_MOSI") (class "Default")
      (node (ref "U10") (pin "8") (pinfunction "SDATA_8") (pintype "input"))
      (node (ref "U6") (pin "28") (pinfunction "PB15_28") (pintype "bidirectional"))
    )
    (net (code "18") (name "/SPI2_NSS") (class "Default")
      (node (ref "U10") (pin "9") (pinfunction "FSYNC_9") (pintype "input"))
      (node (ref "U6") (pin "25") (pinfunction "PB12_25") (pintype "bidirectional"))
    )
    (net (code "19") (name "/SPI2_SCK") (class "Default")
      (node (ref "U10") (pin "7") (pinfunction "SCLK_7") (pintype "input"))
      (node (ref "U6") (pin "26") (pinfunction "PB13_26") (pintype "bidirectional"))
    )
    (net (code "20") (name "/USB+DATA") (class "Default")
      (node (ref "U6") (pin "33") (pinfunction "PA12_33") (pintype "bidirectional"))
      (node (ref "Uiso1") (pin "10") (pinfunction "DD+_10") (pintype "passive"))
    )
    (net (code "21") (name "/USB-DATA") (class "Default")
      (node (ref "U6") (pin "32") (pinfunction "PA11_32") (pintype "bidirectional"))
      (node (ref "Uiso1") (pin "11") (pinfunction "DD-_11") (pintype "passive"))
    )
    (net (code "22") (name "AGND") (class "Default")
      (node (ref "C12") (pin "2") (pinfunction "2_2") (pintype "passive"))
      (node (ref "C13") (pin "1") (pinfunction "1_1") (pintype "passive"))
      (node (ref "C17") (pin "2") (pinfunction "2_2") (pintype "passive"))
      (node (ref "C18") (pin "2") (pinfunction "2_2") (pintype "passive"))
      (node (ref "C19") (pin "2") (pinfunction "2_2") (pintype "passive"))
      (node (ref "C20") (pin "2") (pinfunction "2_2") (pintype "passive"))
      (node (ref "C21") (pin "2") (pinfunction "2_2") (pintype "passive"))
      (node (ref "C22") (pin "2") (pinfunction "2_2") (pintype "passive"))
      (node (ref "C23") (pin "2") (pinfunction "2_2") (pintype "passive"))
      (node (ref "C24") (pin "2") (pinfunction "2_2") (pintype "passive"))
      (node (ref "C28") (pin "2") (pinfunction "2_2") (pintype "passive"))
      (node (ref "C29") (pin "2") (pinfunction "2_2") (pintype "passive"))
      (node (ref "C30") (pin "2") (pinfunction "2_2") (pintype "passive"))
      (node (ref "C31") (pin "2") (pinfunction "2_2") (pintype "passive"))
      (node (ref "C32") (pin "2") (pinfunction "2_2") (pintype "passive"))
      (node (ref "C33") (pin "2") (pinfunction "2_2") (pintype "passive"))
      (node (ref "C34") (pin "2") (pinfunction "2_2") (pintype "passive"))
      (node (ref "C43") (pin "1") (pinfunction "1_1") (pintype "passive"))
      (node (ref "C44") (pin "1") (pinfunction "1_1") (pintype "passive"))
      (node (ref "C45") (pin "1") (pinfunction "1_1") (pintype "passive"))
      (node (ref "C46") (pin "1") (pinfunction "1_1") (pintype "passive"))
      (node (ref "C47") (pin "1") (pinfunction "1_1") (pintype "passive"))
      (node (ref "C48") (pin "1") (pinfunction "1_1") (pintype "passive"))
      (node (ref "C49") (pin "1") (pinfunction "1_1") (pintype "passive"))
      (node (ref "C50") (pin "1") (pinfunction "1_1") (pintype "passive"))
      (node (ref "ESD10") (pin "1") (pinfunction "1_1") (pintype "passive"))
      (node (ref "ESD12") (pin "1") (pinfunction "1_1") (pintype "passive"))
      (node (ref "ESD13") (pin "1") (pinfunction "1_1") (pintype "passive"))
      (node (ref "ESD14") (pin "1") (pinfunction "1_1") (pintype "passive"))
      (node (ref "ESD15") (pin "1") (pinfunction "1_1") (pintype "passive"))
      (node (ref "ESD6") (pin "1") (pinfunction "1_1") (pintype "passive"))
      (node (ref "ESD8") (pin "1") (pinfunction "1_1") (pintype "passive"))
      (node (ref "Jumper1") (pin "2") (pinfunction "2_2") (pintype "passive"))
      (node (ref "Jumper2") (pin "2") (pinfunction "2_2") (pintype "passive"))
      (node (ref "P1") (pin "2") (pinfunction "GND_2") (pintype "power_in"))
      (node (ref "P1") (pin "3") (pinfunction "GND_3") (pintype "power_in"))
      (node (ref "P1") (pin "4") (pinfunction "GND_4") (pintype "power_in"))
      (node (ref "P1") (pin "5") (pinfunction "GND_5") (pintype "power_in"))
      (node (ref "P2") (pin "2") (pinfunction "GND_2") (pintype "power_in"))
      (node (ref "P2") (pin "3") (pinfunction "GND_3") (pintype "power_in"))
      (node (ref "P2") (pin "4") (pinfunction "GND_4") (pintype "power_in"))
      (node (ref "P2") (pin "5") (pinfunction "GND_5") (pintype "power_in"))
      (node (ref "P3") (pin "2") (pinfunction "GND_2") (pintype "power_in"))
      (node (ref "P3") (pin "3") (pinfunction "GND_3") (pintype "power_in"))
      (node (ref "P3") (pin "4") (pinfunction "GND_4") (pintype "power_in"))
      (node (ref "P3") (pin "5") (pinfunction "GND_5") (pintype "power_in"))
      (node (ref "P4") (pin "2") (pinfunction "GND_2") (pintype "power_in"))
      (node (ref "P4") (pin "3") (pinfunction "GND_3") (pintype "power_in"))
      (node (ref "P4") (pin "4") (pinfunction "GND_4") (pintype "power_in"))
      (node (ref "P4") (pin "5") (pinfunction "GND_5") (pintype "power_in"))
      (node (ref "P5") (pin "1") (pinfunction "1_1") (pintype "passive"))
      (node (ref "P5") (pin "11") (pinfunction "11_11") (pintype "passive"))
      (node (ref "P5") (pin "3") (pinfunction "3_3") (pintype "passive"))
      (node (ref "P5") (pin "5") (pinfunction "5_5") (pintype "passive"))
      (node (ref "P5") (pin "7") (pinfunction "7_7") (pintype "passive"))
      (node (ref "P5") (pin "9") (pinfunction "9_9") (pintype "passive"))
      (node (ref "R14") (pin "2") (pinfunction "2_2") (pintype "passive"))
      (node (ref "R18") (pin "1") (pinfunction "Force_1") (pintype "passive"))
      (node (ref "R18") (pin "2") (pinfunction "Sense_2") (pintype "passive"))
      (node (ref "R20") (pin "1") (pinfunction "A_1") (pintype "passive"))
      (node (ref "R24") (pin "2") (pinfunction "2_2") (pintype "passive"))
      (node (ref "T1") (pin "6") (pinfunction "6_6") (pintype "passive"))
      (node (ref "U18") (pin "5") (pinfunction "IMONN_5") (pintype "output"))
      (node (ref "U18") (pin "8") (pinfunction "GND_8") (pintype "power_in"))
      (node (ref "U2") (pin "5") (pinfunction "IN_B+_5") (pintype "input"))
      (node (ref "U3") (pin "14") (pinfunction "AGND-TNH_14") (pintype "passive"))
      (node (ref "U3") (pin "2") (pinfunction "AGND_2") (pintype "passive"))
      (node (ref "U3") (pin "35") (pinfunction "AGND_35") (pintype "passive"))
      (node (ref "U3") (pin "38") (pinfunction "AGND_38") (pintype "passive"))
      (node (ref "U3") (pin "40") (pinfunction "AGND_40") (pintype "passive"))
      (node (ref "U3") (pin "42") (pinfunction "AGND_42") (pintype "passive"))
      (node (ref "U3") (pin "43") (pinfunction "AGND_43") (pintype "passive"))
      (node (ref "U3") (pin "46") (pinfunction "AGND_46") (pintype "passive"))
      (node (ref "U3") (pin "47") (pinfunction "AGND_47") (pintype "passive"))
      (node (ref "U3") (pin "8") (pinfunction "AGND-OUT_8") (pintype "passive"))
    )
    (net (code "23") (name "DAC_AVDD") (class "Default")
      (node (ref "C24") (pin "1") (pinfunction "1_1") (pintype "passive"))
      (node (ref "R22") (pin "1") (pinfunction "A_1") (pintype "passive"))
      (node (ref "U3") (pin "39") (pinfunction "AVDD_39") (pintype "power_in"))
      (node (ref "U3") (pin "41") (pinfunction "AVDD_41") (pintype "power_in"))
    )
    (net (code "24") (name "DAC_DVDD") (class "Default")
      (node (ref "C25") (pin "1") (pinfunction "1_1") (pintype "passive"))
      (node (ref "R21") (pin "1") (pinfunction "A_1") (pintype "passive"))
      (node (ref "U3") (pin "27") (pinfunction "DVDD_27") (pintype "power_in"))
    )
    (net (code "25") (name "DAC_IOVDD") (class "Default")
      (node (ref "C27") (pin "1") (pinfunction "1_1") (pintype "passive"))
      (node (ref "R23") (pin "1") (pinfunction "A_1") (pintype "passive"))
      (node (ref "U3") (pin "28") (pinfunction "IOVDD_28") (pintype "power_in"))
    )
    (net (code "26") (name "DAC_VCC") (class "Default")
      (node (ref "C32") (pin "1") (pinfunction "1_1") (pintype "passive"))
      (node (ref "R25") (pin "1") (pinfunction "A_1") (pintype "passive"))
      (node (ref "U3") (pin "45") (pinfunction "VCC_45") (pintype "power_in"))
    )
    (net (code "27") (name "DAC_VSS") (class "Default")
      (node (ref "C34") (pin "1") (pinfunction "1_1") (pintype "passive"))
      (node (ref "R26") (pin "1") (pinfunction "A_1") (pintype "passive"))
      (node (ref "U3") (pin "44") (pinfunction "VSS_44") (pintype "passive"))
    )
    (net (code "28") (name "DGND") (class "Default")
      (node (ref "C11") (pin "2") (pinfunction "2_2") (pintype "passive"))
      (node (ref "C14") (pin "2") (pinfunction "2_2") (pintype "passive"))
      (node (ref "C15") (pin "2") (pinfunction "2_2") (pintype "passive"))
      (node (ref "C16") (pin "2") (pinfunction "2_2") (pintype "passive"))
      (node (ref "C25") (pin "2") (pinfunction "2_2") (pintype "passive"))
      (node (ref "C26") (pin "2") (pinfunction "2_2") (pintype "passive"))
      (node (ref "C27") (pin "2") (pinfunction "2_2") (pintype "passive"))
      (node (ref "C35") (pin "1") (pinfunction "1_1") (pintype "passive"))
      (node (ref "C36") (pin "1") (pinfunction "1_1") (pintype "passive"))
      (node (ref "C37") (pin "1") (pinfunction "1_1") (pintype "passive"))
      (node (ref "C38") (pin "1") (pinfunction "1_1") (pintype "passive"))
      (node (ref "C39") (pin "1") (pinfunction "1_1") (pintype "passive"))
      (node (ref "C4") (pin "2") (pinfunction "2_2") (pintype "passive"))
      (node (ref "C40") (pin "1") (pinfunction "1_1") (pintype "passive"))
      (node (ref "C41") (pin "1") (pinfunction "1_1") (pintype "passive"))
      (node (ref "C42") (pin "1") (pinfunction "1_1") (pintype "passive"))
      (node (ref "C8") (pin "1") (pinfunction "1_1") (pintype "passive"))
      (node (ref "ESD11") (pin "1") (pinfunction "1_1") (pintype "passive"))
      (node (ref "ESD5") (pin "1") (pinfunction "1_1") (pintype "passive"))
      (node (ref "ESD7") (pin "1") (pinfunction "1_1") (pintype "passive"))
      (node (ref "ESD9") (pin "1") (pinfunction "1_1") (pintype "passive"))
      (node (ref "Jumper1") (pin "1") (pinfunction "A_1") (pintype "passive"))
      (node (ref "P6") (pin "4") (pinfunction "4_4") (pintype "passive"))
      (node (ref "R13") (pin "2") (pinfunction "2_2") (pintype "passive"))
      (node (ref "R5") (pin "2") (pinfunction "2_2") (pintype "passive"))
      (node (ref "R6") (pin "1") (pinfunction "A_1") (pintype "passive"))
      (node (ref "R7") (pin "2") (pinfunction "2_2") (pintype "passive"))
      (node (ref "U10") (pin "10") (pinfunction "FSELECT_10") (pintype "input"))
      (node (ref "U10") (pin "11") (pinfunction "PSEL1_11") (pintype "input"))
      (node (ref "U10") (pin "12") (pinfunction "PSEL0_12") (pintype "input"))
      (node (ref "U10") (pin "13") (pinfunction "AGND_13") (pintype "power_in"))
      (node (ref "U10") (pin "5") (pinfunction "DGND_5") (pintype "power_in"))
      (node (ref "U11") (pin "2") (pinfunction "V-_2") (pintype "power_in"))
      (node (ref "U12") (pin "2") (pinfunction "GND_2") (pintype "passive"))
      (node (ref "U13") (pin "2") (pinfunction "-_2") (pintype "passive"))
      (node (ref "U3") (pin "16") (pinfunction "DGND_16") (pintype "passive"))
      (node (ref "U3") (pin "17") (pinfunction "DGND_17") (pintype "passive"))
      (node (ref "U3") (pin "20") (pinfunction "DGND_20") (pintype "passive"))
      (node (ref "U3") (pin "21") (pinfunction "DGND_21") (pintype "passive"))
      (node (ref "U3") (pin "22") (pinfunction "DGND_22") (pintype "passive"))
      (node (ref "U3") (pin "23") (pinfunction "DGND_23") (pintype "passive"))
      (node (ref "U3") (pin "26") (pinfunction "DNGD_26") (pintype "passive"))
      (node (ref "U6") (pin "23") (pinfunction "Vss_1_23") (pintype "power_in"))
      (node (ref "U6") (pin "35") (pinfunction "Vss_2_35") (pintype "power_in"))
      (node (ref "U6") (pin "44") (pinfunction "BOOT0_44") (pintype "input"))
      (node (ref "U6") (pin "47") (pinfunction "Vss_3_47") (pintype "power_in"))
      (node (ref "U6") (pin "8") (pinfunction "Vssa_8") (pintype "power_in"))
      (node (ref "U9") (pin "14") (pinfunction "~{OE}_14") (pintype "input"))
      (node (ref "U9") (pin "8") (pinfunction "GND_8") (pintype "power_in"))
      (node (ref "Uiso1") (pin "15") (pinfunction "GND2_15") (pintype "passive"))
      (node (ref "Uiso1") (pin "9") (pinfunction "GND2_9") (pintype "passive"))
      (node (ref "Z1") (pin "3") (pinfunction "50_3") (pintype "passive"))
    )
    (net (code "29") (name "Net-(F1-Pad1)") (class "Default")
      (node (ref "F1") (pin "1") (pinfunction "1_1") (pintype "passive"))
      (node (ref "J2") (pin "1") (pinfunction "1_1") (pintype "passive"))
    )
    (net (code "30") (name "Net-(F1-Pad2)") (class "Default")
      (node (ref "F1") (pin "2") (pinfunction "2_2") (pintype "passive"))
      (node (ref "T1") (pin "1") (pinfunction "1_1") (pintype "passive"))
    )
    (net (code "31") (name "Net-(J3-Pad1)") (class "Default")
      (node (ref "J3") (pin "1") (pinfunction "1_1") (pintype "passive"))
      (node (ref "T1") (pin "2") (pintype "passive"))
    )
    (net (code "32") (name "Net-(P1-Signal)") (class "Default")
      (node (ref "P1") (pin "1") (pinfunction "Signal_1") (pintype "input"))
      (node (ref "R10") (pin "1") (pinfunction "A_1") (pintype "passive"))
    )
    (net (code "33") (name "Net-(P2-Signal)") (class "Default")
      (node (ref "P2") (pin "1") (pinfunction "Signal_1") (pintype "input"))
      (node (ref "R12") (pin "2") (pinfunction "2_2") (pintype "passive"))
      (node (ref "R15") (pin "1") (pinfunction "A_1") (pintype "passive"))
    )
    (net (code "34") (name "Net-(P3-Signal)") (class "Default")
      (node (ref "P3") (pin "1") (pinfunction "Signal_1") (pintype "input"))
      (node (ref "R15") (pin "2") (pinfunction "2_2") (pintype "passive"))
      (node (ref "R16") (pin "1") (pinfunction "A_1") (pintype "passive"))
    )
    (net (code "35") (name "Net-(P4-Signal)") (class "Default")
      (node (ref "P4") (pin "1") (pinfunction "Signal_1") (pintype "input"))
      (node (ref "R16") (pin "2") (pinfunction "2_2") (pintype "passive"))
      (node (ref "R17") (pin "1") (pinfunction "A_1") (pintype "passive"))
    )
    (net (code "36") (name "Net-(R1-A)") (class "Default")
      (node (ref "C2") (pin "2") (pinfunction "2_2") (pintype "passive"))
      (node (ref "R1") (pin "1") (pinfunction "A_1") (pintype "passive"))
      (node (ref "R2") (pin "1") (pinfunction "A_1") (pintype "passive"))
      (node (ref "R3") (pin "1") (pinfunction "A_1") (pintype "passive"))
      (node (ref "R4") (pin "1") (pinfunction "A_1") (pintype "passive"))
      (node (ref "U2") (pin "3") (pinfunction "IN_A+_3") (pintype "input"))
    )
    (net (code "37") (name "Net-(R5-A)") (class "Default")
      (node (ref "R5") (pin "1") (pinfunction "A_1") (pintype "passive"))
      (node (ref "U10") (pin "1") (pinfunction "FSADJUST_1") (pintype "input"))
    )
    (net (code "38") (name "Net-(R7-A)") (class "Default")
      (node (ref "R27") (pin "2") (pinfunction "2_2") (pintype "passive"))
      (node (ref "R7") (pin "1") (pinfunction "A_1") (pintype "passive"))
      (node (ref "R8") (pin "1") (pinfunction "A_1") (pintype "passive"))
      (node (ref "U11") (pin "3") (pinfunction "IN+_3") (pintype "input"))
    )
    (net (code "39") (name "Net-(R9-A)") (class "Default")
      (node (ref "R9") (pin "1") (pinfunction "A_1") (pintype "passive"))
      (node (ref "U14") (pin "1") (pinfunction "I/O1_1") (pintype "bidirectional"))
    )
    (net (code "40") (name "Net-(R11-A)") (class "Default")
      (node (ref "R11") (pin "1") (pinfunction "A_1") (pintype "passive"))
      (node (ref "U14") (pin "3") (pinfunction "I/O2_3") (pintype "bidirectional"))
    )
    (net (code "41") (name "Net-(R12-A)") (class "Default")
      (node (ref "P5") (pin "6") (pinfunction "6_6") (pintype "passive"))
      (node (ref "R10") (pin "2") (pinfunction "2_2") (pintype "passive"))
      (node (ref "R12") (pin "1") (pinfunction "A_1") (pintype "passive"))
    )
    (net (code "42") (name "Net-(R13-A)") (class "Default")
      (node (ref "C16") (pin "1") (pinfunction "1_1") (pintype "passive"))
      (node (ref "R13") (pin "1") (pinfunction "A_1") (pintype "passive"))
      (node (ref "U16") (pin "3") (pinfunction "SET_3") (pintype "input"))
    )
    (net (code "43") (name "Net-(R14-A)") (class "Default")
      (node (ref "C19") (pin "1") (pinfunction "1_1") (pintype "passive"))
      (node (ref "R14") (pin "1") (pinfunction "A_1") (pintype "passive"))
      (node (ref "U17") (pin "3") (pinfunction "SET_3") (pintype "input"))
    )
    (net (code "44") (name "Net-(R17-Pad2)") (class "Default")
      (node (ref "R17") (pin "2") (pinfunction "2_2") (pintype "passive"))
      (node (ref "R18") (pin "3") (pinfunction "Sense_3") (pintype "passive"))
      (node (ref "R18") (pin "4") (pinfunction "Force_4") (pintype "passive"))
    )
    (net (code "45") (name "Net-(R19-A)") (class "Default")
      (node (ref "C13") (pin "2") (pinfunction "2_2") (pintype "passive"))
      (node (ref "C20") (pin "1") (pinfunction "1_1") (pintype "passive"))
      (node (ref "R19") (pin "1") (pinfunction "A_1") (pintype "passive"))
      (node (ref "U15") (pin "2") (pinfunction "-_2") (pintype "passive"))
      (node (ref "U18") (pin "1") (pinfunction "IN_1") (pintype "input"))
      (node (ref "U18") (pin "11") (pinfunction "IN_11") (pintype "input"))
      (node (ref "U18") (pin "2") (pinfunction "IN_2") (pintype "input"))
      (node (ref "U18") (pin "4") (pinfunction "IMONP_4") (pintype "output"))
      (node (ref "U18") (pin "6") (pinfunction "*SHDN_6") (pintype "output"))
    )
    (net (code "46") (name "Net-(R24-A)") (class "Default")
      (node (ref "C30") (pin "1") (pinfunction "1_1") (pintype "passive"))
      (node (ref "R24") (pin "1") (pinfunction "A_1") (pintype "passive"))
      (node (ref "U19") (pin "3") (pinfunction "SET_3") (pintype "input"))
    )
    (net (code "47") (name "Net-(R27-A)") (class "Default")
      (node (ref "R27") (pin "1") (pinfunction "A_1") (pintype "passive"))
      (node (ref "U11") (pin "1") (pinfunction "OUT_1") (pintype "output"))
      (node (ref "U9") (pin "11") (pinfunction "CCLK_11") (pintype "input"))
      (node (ref "U9") (pin "13") (pinfunction "RCLK_13") (pintype "input"))
    )
    (net (code "48") (name "Net-(T1-Pad3)") (class "Default")
      (node (ref "T1") (pin "3") (pinfunction "3_3") (pintype "passive"))
      (node (ref "U13") (pin "4") (pinfunction "~_4") (pintype "passive"))
    )
    (net (code "49") (name "Net-(T1-Pad4)") (class "Default")
      (node (ref "T1") (pin "4") (pinfunction "4_4") (pintype "passive"))
      (node (ref "U13") (pin "3") (pinfunction "~_3") (pintype "passive"))
    )
    (net (code "50") (name "Net-(T1-Pad5)") (class "Default")
      (node (ref "T1") (pin "5") (pinfunction "5_5") (pintype "passive"))
      (node (ref "U15") (pin "4") (pinfunction "~_4") (pintype "passive"))
    )
    (net (code "51") (name "Net-(T1-Pad7)") (class "Default")
      (node (ref "T1") (pin "7") (pinfunction "7_7") (pintype "passive"))
      (node (ref "U15") (pin "3") (pinfunction "~_3") (pintype "passive"))
    )
    (net (code "52") (name "Net-(U1A-VOUT)") (class "Default")
      (node (ref "R1") (pin "2") (pinfunction "2_2") (pintype "passive"))
      (node (ref "U1") (pin "6") (pinfunction "VOUT_6") (pintype "output"))
    )
    (net (code "53") (name "Net-(U2A-IN_A-)") (class "Default")
      (node (ref "U2") (pin "1") (pinfunction "OUT_A_1") (pintype "output"))
      (node (ref "U2") (pin "12") (pinfunction "IN_D+_12") (pintype "input"))
      (node (ref "U2") (pin "2") (pinfunction "IN_A-_2") (pintype "input"))
      (node (ref "U3") (pin "10") (pinfunction "ROFS_10") (pintype "passive"))
    )
    (net (code "54") (name "Net-(U2B-IN_B-)") (class "Default")
      (node (ref "U2") (pin "6") (pinfunction "IN_B-_6") (pintype "input"))
      (node (ref "U3") (pin "11") (pinfunction "RCM_11") (pintype "passive"))
    )
    (net (code "55") (name "Net-(U2B-OUT_B)") (class "Default")
      (node (ref "U2") (pin "10") (pinfunction "IN_C+_10") (pintype "input"))
      (node (ref "U2") (pin "7") (pinfunction "OUT_B_7") (pintype "output"))
      (node (ref "U3") (pin "9") (pinfunction "RFB_9") (pintype "passive"))
    )
    (net (code "56") (name "Net-(U2C-IN_C-)") (class "Default")
      (node (ref "C3") (pin "2") (pinfunction "2_2") (pintype "passive"))
      (node (ref "U2") (pin "9") (pinfunction "IN_C-_9") (pintype "input"))
      (node (ref "U3") (pin "6") (pinfunction "REFNS_6") (pintype "passive"))
    )
    (net (code "57") (name "Net-(U2C-OUT_C)") (class "Default")
      (node (ref "C3") (pin "1") (pinfunction "1_1") (pintype "passive"))
      (node (ref "U2") (pin "8") (pinfunction "OUT_C_8") (pintype "output"))
      (node (ref "U3") (pin "5") (pinfunction "REFNF_5") (pintype "passive"))
    )
    (net (code "58") (name "Net-(U2D-IN_D-)") (class "Default")
      (node (ref "C1") (pin "1") (pinfunction "1_1") (pintype "passive"))
      (node (ref "U2") (pin "13") (pinfunction "IN_D-_13") (pintype "input"))
      (node (ref "U3") (pin "4") (pinfunction "REFPS_4") (pintype "passive"))
    )
    (net (code "59") (name "Net-(U2D-OUT_D)") (class "Default")
      (node (ref "C1") (pin "2") (pinfunction "2_2") (pintype "passive"))
      (node (ref "U2") (pin "14") (pinfunction "OUT_D_14") (pintype "output"))
      (node (ref "U3") (pin "3") (pinfunction "REFPF_3") (pintype "passive"))
    )
    (net (code "60") (name "Net-(U3A-ALARM)") (class "Default")
      (node (ref "RN2") (pin "3") (pinfunction "3_3") (pintype "passive"))
      (node (ref "U3") (pin "19") (pinfunction "ALARM_19") (pintype "passive"))
    )
    (net (code "61") (name "Net-(U3A-CLR)") (class "Default")
      (node (ref "RN2") (pin "4") (pinfunction "4_4") (pintype "passive"))
      (node (ref "U3") (pin "30") (pinfunction "CLR_30") (pintype "passive"))
    )
    (net (code "62") (name "Net-(U3A-LDAC)") (class "Default")
      (node (ref "RN2") (pin "2") (pinfunction "2_2") (pintype "passive"))
      (node (ref "U3") (pin "18") (pinfunction "LDAC_18") (pintype "passive"))
    )
    (net (code "63") (name "Net-(U3A-OUT)") (class "Default")
      (node (ref "U3") (pin "7") (pinfunction "OUT_7") (pintype "output"))
      (node (ref "U5") (pin "3") (pinfunction "IN+_3") (pintype "input"))
    )
    (net (code "64") (name "Net-(U3A-SCLK)") (class "Default")
      (node (ref "RN1") (pin "1") (pinfunction "1_1") (pintype "passive"))
      (node (ref "U3") (pin "31") (pinfunction "SCLK_31") (pintype "passive"))
    )
    (net (code "65") (name "Net-(U3A-SDIN)") (class "Default")
      (node (ref "RN1") (pin "2") (pinfunction "2_2") (pintype "passive"))
      (node (ref "U3") (pin "32") (pinfunction "SDIN_32") (pintype "passive"))
    )
    (net (code "66") (name "Net-(U3A-SDO)") (class "Default")
      (node (ref "RN1") (pin "4") (pinfunction "4_4") (pintype "passive"))
      (node (ref "U3") (pin "34") (pinfunction "SDO_34") (pintype "passive"))
    )
    (net (code "67") (name "Net-(U3A-SYNC)") (class "Default")
      (node (ref "RN1") (pin "3") (pinfunction "3_3") (pintype "passive"))
      (node (ref "U3") (pin "33") (pinfunction "SYNC_33") (pintype "passive"))
    )
    (net (code "68") (name "Net-(U4A-VOUT)") (class "Default")
      (node (ref "R2") (pin "2") (pinfunction "2_2") (pintype "passive"))
      (node (ref "U4") (pin "6") (pinfunction "VOUT_6") (pintype "output"))
    )
    (net (code "69") (name "Net-(U5A-IN-)") (class "Default")
      (node (ref "P5") (pin "8") (pinfunction "8_8") (pintype "passive"))
      (node (ref "U5") (pin "2") (pinfunction "IN-_2") (pintype "input"))
      (node (ref "U5") (pin "6") (pinfunction "OUT_6") (pintype "output"))
    )
    (net (code "70") (name "Net-(U6-OSC_IN)") (class "Default")
      (node (ref "U6") (pin "5") (pinfunction "OSC_IN_5") (pintype "input"))
      (node (ref "Z1") (pin "2") (pinfunction "2_2") (pintype "passive"))
    )
    (net (code "71") (name "Net-(U6-OSC_OUT)") (class "Default")
      (node (ref "U6") (pin "6") (pinfunction "OSC_OUT_6") (pintype "output"))
      (node (ref "Z1") (pin "1") (pinfunction "50_1") (pintype "passive"))
    )
    (net (code "72") (name "Net-(U6-SWCLK{slash}PA14)") (class "Default")
      (node (ref "P6") (pin "2") (pinfunction "2_2") (pintype "passive"))
      (node (ref "U6") (pin "37") (pinfunction "SWCLK/PA14_37") (pintype "bidirectional"))
    )
    (net (code "73") (name "Net-(U6-SWDIO{slash}PA13)") (class "Default")
      (node (ref "P6") (pin "3") (pinfunction "3_3") (pintype "passive"))
      (node (ref "U6") (pin "34") (pinfunction "SWDIO/PA13_34") (pintype "bidirectional"))
    )
    (net (code "74") (name "Net-(U7A-VOUT)") (class "Default")
      (node (ref "R3") (pin "2") (pinfunction "2_2") (pintype "passive"))
      (node (ref "U7") (pin "6") (pinfunction "VOUT_6") (pintype "output"))
    )
    (net (code "75") (name "Net-(U8A-VOUT)") (class "Default")
      (node (ref "R4") (pin "2") (pinfunction "2_2") (pintype "passive"))
      (node (ref "U8") (pin "6") (pinfunction "VOUT_6") (pintype "output"))
    )
    (net (code "76") (name "Net-(U10-COMP)") (class "Default")
      (node (ref "C5") (pin "2") (pinfunction "2_2") (pintype "passive"))
      (node (ref "U10") (pin "16") (pinfunction "COMP_16") (pintype "passive"))
    )
    (net (code "77") (name "Net-(U10-IOUT)") (class "Default")
      (node (ref "R6") (pin "2") (pinfunction "2_2") (pintype "passive"))
      (node (ref "U10") (pin "14") (pinfunction "IOUT_14") (pintype "output"))
      (node (ref "U11") (pin "4") (pinfunction "IN-_4") (pintype "input"))
    )
    (net (code "78") (name "Net-(U10-MCLK)") (class "Default")
      (node (ref "U10") (pin "6") (pinfunction "MCLK_6") (pintype "input"))
      (node (ref "U12") (pin "3") (pinfunction "CMOS_OUTPUT_3") (pintype "output"))
    )
    (net (code "79") (name "Net-(U10-REFIN)") (class "Default")
      (node (ref "C4") (pin "1") (pinfunction "1_1") (pintype "passive"))
      (node (ref "U10") (pin "2") (pinfunction "REFIN_2") (pintype "input"))
      (node (ref "U10") (pin "3") (pinfunction "REFOUT_3") (pintype "output"))
    )
    (net (code "80") (name "Net-(U13-+)") (class "Default")
      (node (ref "C11") (pin "1") (pinfunction "1_1") (pintype "passive"))
      (node (ref "C14") (pin "1") (pinfunction "1_1") (pintype "passive"))
      (node (ref "U13") (pin "1") (pinfunction "+_1") (pintype "passive"))
      (node (ref "U16") (pin "4") (pinfunction "VCONTROL_4") (pintype "power_in"))
      (node (ref "U16") (pin "5") (pinfunction "IN_5") (pintype "power_in"))
      (node (ref "U16") (pin "6") (pinfunction "IN_6") (pintype "power_in"))
    )
    (net (code "81") (name "Net-(U15-+)") (class "Default")
      (node (ref "C12") (pin "1") (pinfunction "1_1") (pintype "passive"))
      (node (ref "C17") (pin "1") (pinfunction "1_1") (pintype "passive"))
      (node (ref "C28") (pin "1") (pinfunction "1_1") (pintype "passive"))
      (node (ref "U15") (pin "1") (pinfunction "+_1") (pintype "passive"))
      (node (ref "U17") (pin "4") (pinfunction "VCONTROL_4") (pintype "power_in"))
      (node (ref "U17") (pin "5") (pinfunction "IN_5") (pintype "power_in"))
      (node (ref "U17") (pin "6") (pinfunction "IN_6") (pintype "power_in"))
      (node (ref "U19") (pin "4") (pinfunction "VCONTROL_4") (pintype "power_in"))
      (node (ref "U19") (pin "5") (pinfunction "IN_5") (pintype "power_in"))
      (node (ref "U19") (pin "6") (pinfunction "IN_6") (pintype "power_in"))
    )
    (net (code "82") (name "Net-(U18-ILIM)") (class "Default")
      (node (ref "R19") (pin "2") (pinfunction "2_2") (pintype "passive"))
      (node (ref "U18") (pin "3") (pinfunction "ILIM_3") (pintype "passive"))
    )
    (net (code "83") (name "Net-(U18-SET)") (class "Default")
      (node (ref "C22") (pin "1") (pinfunction "1_1") (pintype "passive"))
      (node (ref "R20") (pin "2") (pinfunction "2_2") (pintype "passive"))
      (node (ref "U18") (pin "7") (pinfunction "SET_7") (pintype "input"))
    )
    (net (code "84") (name "Net-(Uiso1-PDEN)") (class "Default")
      (node (ref "C9") (pin "2") (pinfunction "2_2") (pintype "passive"))
      (node (ref "Uiso1") (pin "3") (pinfunction "VDD1_3") (pintype "passive"))
      (node (ref "Uiso1") (pin "4") (pinfunction "PDEN_4") (pintype "passive"))
      (node (ref "Uiso1") (pin "5") (pinfunction "SPU_5") (pintype "passive"))
    )
    (net (code "85") (name "Net-(Uiso1-UD-)") (class "Default")
      (node (ref "U14") (pin "6") (pinfunction "I/O1_6") (pintype "bidirectional"))
      (node (ref "Uiso1") (pin "6") (pinfunction "UD-_6") (pintype "passive"))
    )
    (net (code "86") (name "Net-(Uiso1-US+)") (class "Default")
      (node (ref "U14") (pin "4") (pinfunction "I/O2_4") (pintype "bidirectional"))
      (node (ref "Uiso1") (pin "7") (pinfunction "US+_7") (pintype "passive"))
    )
    (net (code "87") (name "REFGND") (class "Default")
      (node (ref "C2") (pin "1") (pinfunction "1_1") (pintype "passive"))
      (node (ref "C51") (pin "1") (pinfunction "1_1") (pintype "passive"))
      (node (ref "C52") (pin "1") (pinfunction "1_1") (pintype "passive"))
      (node (ref "C53") (pin "1") (pinfunction "1_1") (pintype "passive"))
      (node (ref "C54") (pin "1") (pinfunction "1_1") (pintype "passive"))
      (node (ref "C55") (pin "1") (pinfunction "1_1") (pintype "passive"))
      (node (ref "ESD1") (pin "1") (pinfunction "1_1") (pintype "passive"))
      (node (ref "ESD2") (pin "1") (pinfunction "1_1") (pintype "passive"))
      (node (ref "ESD3") (pin "1") (pinfunction "1_1") (pintype "passive"))
      (node (ref "ESD4") (pin "1") (pinfunction "1_1") (pintype "passive"))
      (node (ref "Jumper2") (pin "1") (pinfunction "A_1") (pintype "passive"))
      (node (ref "U1") (pin "4") (pinfunction "COM_4") (pintype "power_in"))
      (node (ref "U4") (pin "4") (pinfunction "COM_4") (pintype "power_in"))
      (node (ref "U7") (pin "4") (pinfunction "COM_4") (pintype "power_in"))
      (node (ref "U8") (pin "4") (pinfunction "COM_4") (pintype "power_in"))
    )
    (net (code "88") (name "USB_GND") (class "Default")
      (node (ref "C10") (pin "1") (pinfunction "1_1") (pintype "passive"))
      (node (ref "C9") (pin "1") (pinfunction "1_1") (pintype "passive"))
      (node (ref "J1") (pin "5") (pinfunction "GND_5") (pintype "passive"))
      (node (ref "J1") (pin "MH1") (pinfunction "Tab_MH1") (pintype "passive"))
      (node (ref "J1") (pin "MH2") (pinfunction "Tab_MH2") (pintype "passive"))
      (node (ref "J1") (pin "MH3") (pinfunction "Tab_MH3") (pintype "passive"))
      (node (ref "J1") (pin "MH4") (pinfunction "Tab_MH4") (pintype "passive"))
      (node (ref "U14") (pin "2") (pinfunction "GND_2") (pintype "power_in"))
      (node (ref "Uiso1") (pin "2") (pinfunction "GND1_2") (pintype "passive"))
      (node (ref "Uiso1") (pin "8") (pinfunction "GND1_8") (pintype "passive"))
    )
    (net (code "89") (name "unconnected-(ESD16-Pad1)") (class "Default")
      (node (ref "ESD16") (pin "1") (pinfunction "1_1") (pintype "passive"))
    )
    (net (code "90") (name "unconnected-(J1-NC-Pad4)") (class "Default")
      (node (ref "J1") (pin "4") (pinfunction "NC_4") (pintype "passive"))
    )
    (net (code "91") (name "unconnected-(U1A-NR-Pad8)") (class "Default")
      (node (ref "U1") (pin "8") (pinfunction "NR_8") (pintype "input"))
    )
    (net (code "92") (name "unconnected-(U1A-TRIM-Pad5)") (class "Default")
      (node (ref "U1") (pin "5") (pinfunction "TRIM_5") (pintype "input"))
    )
    (net (code "93") (name "unconnected-(U2B-V+-Pad4)") (class "Default")
      (node (ref "U2") (pin "4") (pinfunction "V+_4") (pintype "power_in"))
    )
    (net (code "94") (name "unconnected-(U2B-V--Pad11)") (class "Default")
      (node (ref "U2") (pin "11") (pinfunction "V-_11") (pintype "power_in"))
    )
    (net (code "95") (name "unconnected-(U2C-V+-Pad4)") (class "Default")
      (node (ref "U2") (pin "4") (pinfunction "V+_4") (pintype "power_in"))
    )
    (net (code "96") (name "unconnected-(U2C-V--Pad11)") (class "Default")
      (node (ref "U2") (pin "11") (pinfunction "V-_11") (pintype "power_in"))
    )
    (net (code "97") (name "unconnected-(U2D-V+-Pad4)") (class "Default")
      (node (ref "U2") (pin "4") (pinfunction "V+_4") (pintype "power_in"))
    )
    (net (code "98") (name "unconnected-(U2D-V--Pad11)") (class "Default")
      (node (ref "U2") (pin "11") (pinfunction "V-_11") (pintype "power_in"))
    )
    (net (code "99") (name "unconnected-(U4A-NR-Pad8)") (class "Default")
      (node (ref "U4") (pin "8") (pinfunction "NR_8") (pintype "input"))
    )
    (net (code "100") (name "unconnected-(U4A-TRIM-Pad5)") (class "Default")
      (node (ref "U4") (pin "5") (pinfunction "TRIM_5") (pintype "input"))
    )
    (net (code "101") (name "unconnected-(U6-I2C2_SCL-Pad21)") (class "Default")
      (node (ref "U6") (pin "21") (pinfunction "I2C2_SCL_21") (pintype "bidirectional"))
    )
    (net (code "102") (name "unconnected-(U6-I2C2_SDA-Pad22)") (class "Default")
      (node (ref "U6") (pin "22") (pinfunction "I2C2_SDA_22") (pintype "bidirectional"))
    )
    (net (code "103") (name "unconnected-(U6-NRST-Pad7)") (class "Default")
      (node (ref "U6") (pin "7") (pinfunction "NRST_7") (pintype "bidirectional"))
    )
    (net (code "104") (name "unconnected-(U6-OSC32_IN-Pad3)") (class "Default")
      (node (ref "U6") (pin "3") (pinfunction "OSC32_IN_3") (pintype "input"))
    )
    (net (code "105") (name "unconnected-(U6-OSC32_OUT-Pad4)") (class "Default")
      (node (ref "U6") (pin "4") (pinfunction "OSC32_OUT_4") (pintype "output"))
    )
    (net (code "106") (name "unconnected-(U6-PA3-Pad13)") (class "Default")
      (node (ref "U6") (pin "13") (pinfunction "PA3_13") (pintype "bidirectional"))
    )
    (net (code "107") (name "unconnected-(U6-PA8-Pad29)") (class "Default")
      (node (ref "U6") (pin "29") (pinfunction "PA8_29") (pintype "bidirectional"))
    )
    (net (code "108") (name "unconnected-(U6-PA9-Pad30)") (class "Default")
      (node (ref "U6") (pin "30") (pinfunction "PA9_30") (pintype "bidirectional"))
    )
    (net (code "109") (name "unconnected-(U6-PA10-Pad31)") (class "Default")
      (node (ref "U6") (pin "31") (pinfunction "PA10_31") (pintype "bidirectional"))
    )
    (net (code "110") (name "unconnected-(U6-PA15-Pad38)") (class "Default")
      (node (ref "U6") (pin "38") (pinfunction "PA15_38") (pintype "bidirectional"))
    )
    (net (code "111") (name "unconnected-(U6-PB0-Pad18)") (class "Default")
      (node (ref "U6") (pin "18") (pinfunction "PB0_18") (pintype "bidirectional"))
    )
    (net (code "112") (name "unconnected-(U6-PB1-Pad19)") (class "Default")
      (node (ref "U6") (pin "19") (pinfunction "PB1_19") (pintype "bidirectional"))
    )
    (net (code "113") (name "unconnected-(U6-PB2{slash}BOOT1-Pad20)") (class "Default")
      (node (ref "U6") (pin "20") (pinfunction "PB2/BOOT1_20") (pintype "bidirectional"))
    )
    (net (code "114") (name "unconnected-(U6-PB6-Pad42)") (class "Default")
      (node (ref "U6") (pin "42") (pinfunction "PB6_42") (pintype "bidirectional"))
    )
    (net (code "115") (name "unconnected-(U6-PB7-Pad43)") (class "Default")
      (node (ref "U6") (pin "43") (pinfunction "PB7_43") (pintype "bidirectional"))
    )
    (net (code "116") (name "unconnected-(U6-PB8-Pad45)") (class "Default")
      (node (ref "U6") (pin "45") (pinfunction "PB8_45") (pintype "bidirectional"))
    )
    (net (code "117") (name "unconnected-(U6-PB9-Pad46)") (class "Default")
      (node (ref "U6") (pin "46") (pinfunction "PB9_46") (pintype "bidirectional"))
    )
    (net (code "118") (name "unconnected-(U6-PB14-Pad27)") (class "Default")
      (node (ref "U6") (pin "27") (pinfunction "PB14_27") (pintype "bidirectional"))
    )
    (net (code "119") (name "unconnected-(U6-PC13-Pad2)") (class "Default")
      (node (ref "U6") (pin "2") (pinfunction "PC13_2") (pintype "bidirectional"))
    )
    (net (code "120") (name "unconnected-(U6-SPI1_MISO-Pad40)") (class "Default")
      (node (ref "U6") (pin "40") (pinfunction "SPI1_MISO_40") (pintype "bidirectional"))
    )
    (net (code "121") (name "unconnected-(U6-SPI1_MOSI-Pad41)") (class "Default")
      (node (ref "U6") (pin "41") (pinfunction "SPI1_MOSI_41") (pintype "bidirectional"))
    )
    (net (code "122") (name "unconnected-(U6-Thermal-PadGND)") (class "Default")
      (node (ref "U6") (pin "GND") (pinfunction "Thermal_GND") (pintype "power_in"))
    )
    (net (code "123") (name "unconnected-(U6-Vlcd-Pad1)") (class "Default")
      (node (ref "U6") (pin "1") (pinfunction "Vlcd_1") (pintype "power_in"))
    )
    (net (code "124") (name "unconnected-(U7A-NR-Pad8)") (class "Default")
      (node (ref "U7") (pin "8") (pinfunction "NR_8") (pintype "input"))
    )
    (net (code "125") (name "unconnected-(U7A-TRIM-Pad5)") (class "Default")
      (node (ref "U7") (pin "5") (pinfunction "TRIM_5") (pintype "input"))
    )
    (net (code "126") (name "unconnected-(U8A-NR-Pad8)") (class "Default")
      (node (ref "U8") (pin "8") (pinfunction "NR_8") (pintype "input"))
    )
    (net (code "127") (name "unconnected-(U8A-TRIM-Pad5)") (class "Default")
      (node (ref "U8") (pin "5") (pinfunction "TRIM_5") (pintype "input"))
    )
    (net (code "128") (name "unconnected-(U9-QA-Pad15)") (class "Default")
      (node (ref "U9") (pin "15") (pinfunction "QA_15") (pintype "output"))
    )
    (net (code "129") (name "unconnected-(U9-QB-Pad1)") (class "Default")
      (node (ref "U9") (pin "1") (pinfunction "QB_1") (pintype "output"))
    )
    (net (code "130") (name "unconnected-(U9-QC-Pad2)") (class "Default")
      (node (ref "U9") (pin "2") (pinfunction "QC_2") (pintype "output"))
    )
    (net (code "131") (name "unconnected-(U9-QD-Pad3)") (class "Default")
      (node (ref "U9") (pin "3") (pinfunction "QD_3") (pintype "output"))
    )
    (net (code "132") (name "unconnected-(U9-QE-Pad4)") (class "Default")
      (node (ref "U9") (pin "4") (pinfunction "QE_4") (pintype "output"))
    )
    (net (code "133") (name "unconnected-(U9-QF-Pad5)") (class "Default")
      (node (ref "U9") (pin "5") (pinfunction "QF_5") (pintype "output"))
    )
    (net (code "134") (name "unconnected-(U9-QG-Pad6)") (class "Default")
      (node (ref "U9") (pin "6") (pinfunction "QG_6") (pintype "output"))
    )
    (net (code "135") (name "unconnected-(U9-~{RCO}-Pad9)") (class "Default")
      (node (ref "U9") (pin "9") (pinfunction "~{RCO}_9") (pintype "output"))
    )
    (net (code "136") (name "unconnected-(U12-VC-Pad1)") (class "Default")
      (node (ref "U12") (pin "1") (pinfunction "VC_1") (pintype "passive"))
    )
  )
)
